# mx8m_power.net
KiCad netlist of a schematic drawn in Altium Designer
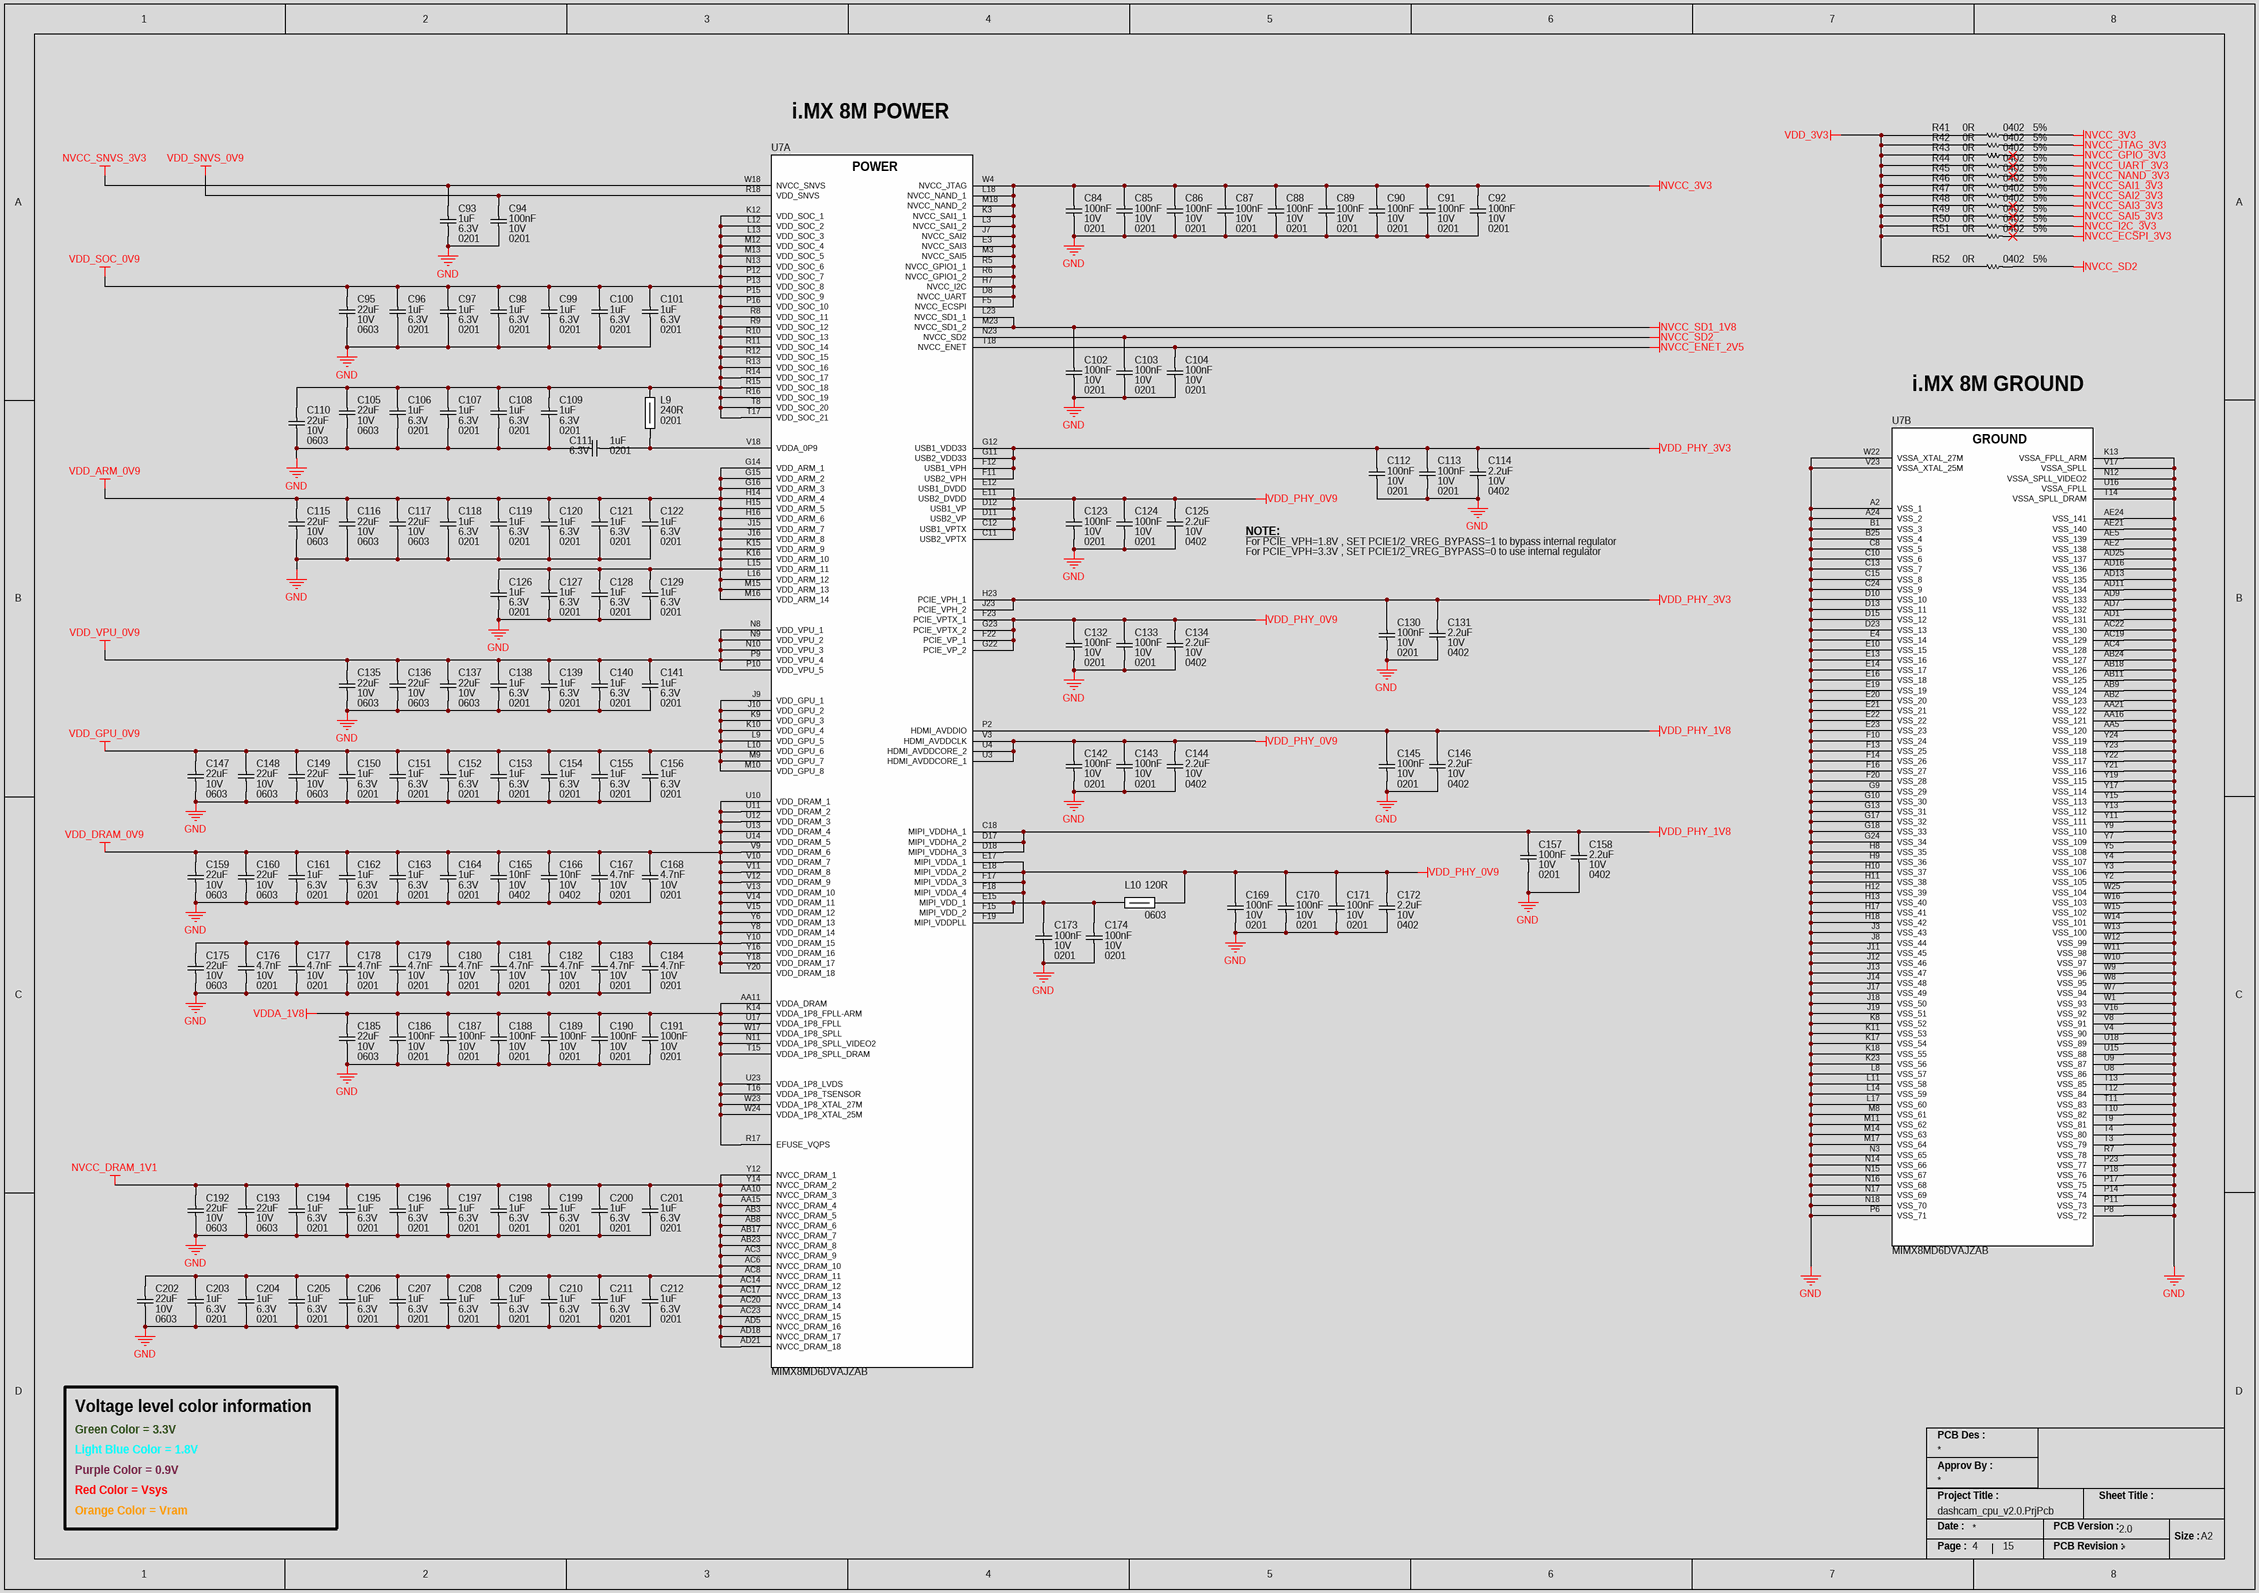
[diagram p0: mx8m_power.SchDoc]

(export (version "E")
  (design (tool "Eeschema 10.0.6"))
  (components
    (comp (ref "C84")
      (value "0201X104K100CT")
      (footprint "CAP_0201_CAPC0603X03N")
      (description "0201 0.1 uF 10 V ±10 %Tolerance X5R Surface Mount Multilayer Ceramic Capacitor")
      (fields
        (field (name "MANUFACTURER") "Walsin Technologies")
        (field (name "TOLERANCE") "10%")
        (field (name "CAPACITANCE") "100nF")
        (field (name "VOLTAGE RATING") "10V")
        (field (name "CASE/PACKAGE") "0201")
      )
      (libsource (lib "Electronic Devices_LIB") (part "CAP_0.1UF_10V_X5R_0201"))
    )
    (comp (ref "C85")
      (value "0201X104K100CT")
      (footprint "CAP_0201_CAPC0603X03N")
      (description "0201 0.1 uF 10 V ±10 %Tolerance X5R Surface Mount Multilayer Ceramic Capacitor")
      (fields
        (field (name "MANUFACTURER") "Walsin Technologies")
        (field (name "TOLERANCE") "10%")
        (field (name "CAPACITANCE") "100nF")
        (field (name "VOLTAGE RATING") "10V")
        (field (name "CASE/PACKAGE") "0201")
      )
      (libsource (lib "Electronic Devices_LIB") (part "CAP_0.1UF_10V_X5R_0201"))
    )
    (comp (ref "C86")
      (value "0201X104K100CT")
      (footprint "CAP_0201_CAPC0603X03N")
      (description "0201 0.1 uF 10 V ±10 %Tolerance X5R Surface Mount Multilayer Ceramic Capacitor")
      (fields
        (field (name "MANUFACTURER") "Walsin Technologies")
        (field (name "TOLERANCE") "10%")
        (field (name "CAPACITANCE") "100nF")
        (field (name "VOLTAGE RATING") "10V")
        (field (name "CASE/PACKAGE") "0201")
      )
      (libsource (lib "Electronic Devices_LIB") (part "CAP_0.1UF_10V_X5R_0201"))
    )
    (comp (ref "C87")
      (value "0201X104K100CT")
      (footprint "CAP_0201_CAPC0603X03N")
      (description "0201 0.1 uF 10 V ±10 %Tolerance X5R Surface Mount Multilayer Ceramic Capacitor")
      (fields
        (field (name "MANUFACTURER") "Walsin Technologies")
        (field (name "TOLERANCE") "10%")
        (field (name "CAPACITANCE") "100nF")
        (field (name "VOLTAGE RATING") "10V")
        (field (name "CASE/PACKAGE") "0201")
      )
      (libsource (lib "Electronic Devices_LIB") (part "CAP_0.1UF_10V_X5R_0201"))
    )
    (comp (ref "C88")
      (value "0201X104K100CT")
      (footprint "CAP_0201_CAPC0603X03N")
      (description "0201 0.1 uF 10 V ±10 %Tolerance X5R Surface Mount Multilayer Ceramic Capacitor")
      (fields
        (field (name "MANUFACTURER") "Walsin Technologies")
        (field (name "TOLERANCE") "10%")
        (field (name "CAPACITANCE") "100nF")
        (field (name "VOLTAGE RATING") "10V")
        (field (name "CASE/PACKAGE") "0201")
      )
      (libsource (lib "Electronic Devices_LIB") (part "CAP_0.1UF_10V_X5R_0201"))
    )
    (comp (ref "C89")
      (value "0201X104K100CT")
      (footprint "CAP_0201_CAPC0603X03N")
      (description "0201 0.1 uF 10 V ±10 %Tolerance X5R Surface Mount Multilayer Ceramic Capacitor")
      (fields
        (field (name "MANUFACTURER") "Walsin Technologies")
        (field (name "TOLERANCE") "10%")
        (field (name "CAPACITANCE") "100nF")
        (field (name "VOLTAGE RATING") "10V")
        (field (name "CASE/PACKAGE") "0201")
      )
      (libsource (lib "Electronic Devices_LIB") (part "CAP_0.1UF_10V_X5R_0201"))
    )
    (comp (ref "C90")
      (value "0201X104K100CT")
      (footprint "CAP_0201_CAPC0603X03N")
      (description "0201 0.1 uF 10 V ±10 %Tolerance X5R Surface Mount Multilayer Ceramic Capacitor")
      (fields
        (field (name "MANUFACTURER") "Walsin Technologies")
        (field (name "TOLERANCE") "10%")
        (field (name "CAPACITANCE") "100nF")
        (field (name "VOLTAGE RATING") "10V")
        (field (name "CASE/PACKAGE") "0201")
      )
      (libsource (lib "Electronic Devices_LIB") (part "CAP_0.1UF_10V_X5R_0201"))
    )
    (comp (ref "C91")
      (value "0201X104K100CT")
      (footprint "CAP_0201_CAPC0603X03N")
      (description "0201 0.1 uF 10 V ±10 %Tolerance X5R Surface Mount Multilayer Ceramic Capacitor")
      (fields
        (field (name "MANUFACTURER") "Walsin Technologies")
        (field (name "TOLERANCE") "10%")
        (field (name "CAPACITANCE") "100nF")
        (field (name "VOLTAGE RATING") "10V")
        (field (name "CASE/PACKAGE") "0201")
      )
      (libsource (lib "Electronic Devices_LIB") (part "CAP_0.1UF_10V_X5R_0201"))
    )
    (comp (ref "C92")
      (value "0201X104K100CT")
      (footprint "CAP_0201_CAPC0603X03N")
      (description "0201 0.1 uF 10 V ±10 %Tolerance X5R Surface Mount Multilayer Ceramic Capacitor")
      (fields
        (field (name "MANUFACTURER") "Walsin Technologies")
        (field (name "TOLERANCE") "10%")
        (field (name "CAPACITANCE") "100nF")
        (field (name "VOLTAGE RATING") "10V")
        (field (name "CASE/PACKAGE") "0201")
      )
      (libsource (lib "Electronic Devices_LIB") (part "CAP_0.1UF_10V_X5R_0201"))
    )
    (comp (ref "C93")
      (value "02016D105MAT2A")
      (footprint "CAP_0201_CAPC0603X03N")
      (description "0201 1 uF 6.3 V ±20 % Tolerance X5R Surface Mount Multilayer Ceramic Capacitor")
      (fields
        (field (name "MANUFACTURER") "Kyocera AVX")
        (field (name "TOLERANCE") "20%")
        (field (name "VOLTAGE RATING (DC)") "6.3V")
        (field (name "CAPACITANCE") "1uF")
        (field (name "CASE/PACKAGE") "0201")
      )
      (libsource (lib "Electronic Devices_LIB") (part "CAP_1UF_6.3V_X5R_0201"))
    )
    (comp (ref "C94")
      (value "0201X104K100CT")
      (footprint "CAP_0201_CAPC0603X03N")
      (description "0201 0.1 uF 10 V ±10 %Tolerance X5R Surface Mount Multilayer Ceramic Capacitor")
      (fields
        (field (name "MANUFACTURER") "Walsin Technologies")
        (field (name "TOLERANCE") "10%")
        (field (name "CAPACITANCE") "100nF")
        (field (name "VOLTAGE RATING") "10V")
        (field (name "CASE/PACKAGE") "0201")
      )
      (libsource (lib "Electronic Devices_LIB") (part "CAP_0.1UF_10V_X5R_0201"))
    )
    (comp (ref "C95")
      (value "C1608X5R1A226M080AC")
      (footprint "CAP_0603_CAPC1608X08N")
      (description "Multilayer Ceramic Capacitor, 22 uF, 10 V, ± 20%, X5R, 0603 [1608 Metric]")
      (fields
        (field (name "MANUFACTURER") "TDK")
        (field (name "TOLERANCE") "20%")
        (field (name "CAPACITANCE") "22uF")
        (field (name "VOLTAGE RATING") "10V")
        (field (name "CASE CODE (IMPERIAL)") "0603")
      )
      (libsource (lib "Electronic Devices_LIB") (part "CAP_22UF_10V_X5R_0603"))
    )
    (comp (ref "C96")
      (value "02016D105MAT2A")
      (footprint "CAP_0201_CAPC0603X03N")
      (description "0201 1 uF 6.3 V ±20 % Tolerance X5R Surface Mount Multilayer Ceramic Capacitor")
      (fields
        (field (name "MANUFACTURER") "Kyocera AVX")
        (field (name "TOLERANCE") "20%")
        (field (name "VOLTAGE RATING (DC)") "6.3V")
        (field (name "CAPACITANCE") "1uF")
        (field (name "CASE/PACKAGE") "0201")
      )
      (libsource (lib "Electronic Devices_LIB") (part "CAP_1UF_6.3V_X5R_0201"))
    )
    (comp (ref "C97")
      (value "02016D105MAT2A")
      (footprint "CAP_0201_CAPC0603X03N")
      (description "0201 1 uF 6.3 V ±20 % Tolerance X5R Surface Mount Multilayer Ceramic Capacitor")
      (fields
        (field (name "MANUFACTURER") "Kyocera AVX")
        (field (name "TOLERANCE") "20%")
        (field (name "VOLTAGE RATING (DC)") "6.3V")
        (field (name "CAPACITANCE") "1uF")
        (field (name "CASE/PACKAGE") "0201")
      )
      (libsource (lib "Electronic Devices_LIB") (part "CAP_1UF_6.3V_X5R_0201"))
    )
    (comp (ref "C98")
      (value "02016D105MAT2A")
      (footprint "CAP_0201_CAPC0603X03N")
      (description "0201 1 uF 6.3 V ±20 % Tolerance X5R Surface Mount Multilayer Ceramic Capacitor")
      (fields
        (field (name "MANUFACTURER") "Kyocera AVX")
        (field (name "TOLERANCE") "20%")
        (field (name "VOLTAGE RATING (DC)") "6.3V")
        (field (name "CAPACITANCE") "1uF")
        (field (name "CASE/PACKAGE") "0201")
      )
      (libsource (lib "Electronic Devices_LIB") (part "CAP_1UF_6.3V_X5R_0201"))
    )
    (comp (ref "C99")
      (value "02016D105MAT2A")
      (footprint "CAP_0201_CAPC0603X03N")
      (description "0201 1 uF 6.3 V ±20 % Tolerance X5R Surface Mount Multilayer Ceramic Capacitor")
      (fields
        (field (name "MANUFACTURER") "Kyocera AVX")
        (field (name "TOLERANCE") "20%")
        (field (name "VOLTAGE RATING (DC)") "6.3V")
        (field (name "CAPACITANCE") "1uF")
        (field (name "CASE/PACKAGE") "0201")
      )
      (libsource (lib "Electronic Devices_LIB") (part "CAP_1UF_6.3V_X5R_0201"))
    )
    (comp (ref "C100")
      (value "02016D105MAT2A")
      (footprint "CAP_0201_CAPC0603X03N")
      (description "0201 1 uF 6.3 V ±20 % Tolerance X5R Surface Mount Multilayer Ceramic Capacitor")
      (fields
        (field (name "MANUFACTURER") "Kyocera AVX")
        (field (name "TOLERANCE") "20%")
        (field (name "VOLTAGE RATING (DC)") "6.3V")
        (field (name "CAPACITANCE") "1uF")
        (field (name "CASE/PACKAGE") "0201")
      )
      (libsource (lib "Electronic Devices_LIB") (part "CAP_1UF_6.3V_X5R_0201"))
    )
    (comp (ref "C101")
      (value "02016D105MAT2A")
      (footprint "CAP_0201_CAPC0603X03N")
      (description "0201 1 uF 6.3 V ±20 % Tolerance X5R Surface Mount Multilayer Ceramic Capacitor")
      (fields
        (field (name "MANUFACTURER") "Kyocera AVX")
        (field (name "TOLERANCE") "20%")
        (field (name "VOLTAGE RATING (DC)") "6.3V")
        (field (name "CAPACITANCE") "1uF")
        (field (name "CASE/PACKAGE") "0201")
      )
      (libsource (lib "Electronic Devices_LIB") (part "CAP_1UF_6.3V_X5R_0201"))
    )
    (comp (ref "C102")
      (value "0201X104K100CT")
      (footprint "CAP_0201_CAPC0603X03N")
      (description "0201 0.1 uF 10 V ±10 %Tolerance X5R Surface Mount Multilayer Ceramic Capacitor")
      (fields
        (field (name "MANUFACTURER") "Walsin Technologies")
        (field (name "TOLERANCE") "10%")
        (field (name "CAPACITANCE") "100nF")
        (field (name "VOLTAGE RATING") "10V")
        (field (name "CASE/PACKAGE") "0201")
      )
      (libsource (lib "Electronic Devices_LIB") (part "CAP_0.1UF_10V_X5R_0201"))
    )
    (comp (ref "C103")
      (value "0201X104K100CT")
      (footprint "CAP_0201_CAPC0603X03N")
      (description "0201 0.1 uF 10 V ±10 %Tolerance X5R Surface Mount Multilayer Ceramic Capacitor")
      (fields
        (field (name "MANUFACTURER") "Walsin Technologies")
        (field (name "TOLERANCE") "10%")
        (field (name "CAPACITANCE") "100nF")
        (field (name "VOLTAGE RATING") "10V")
        (field (name "CASE/PACKAGE") "0201")
      )
      (libsource (lib "Electronic Devices_LIB") (part "CAP_0.1UF_10V_X5R_0201"))
    )
    (comp (ref "C104")
      (value "0201X104K100CT")
      (footprint "CAP_0201_CAPC0603X03N")
      (description "0201 0.1 uF 10 V ±10 %Tolerance X5R Surface Mount Multilayer Ceramic Capacitor")
      (fields
        (field (name "MANUFACTURER") "Walsin Technologies")
        (field (name "TOLERANCE") "10%")
        (field (name "CAPACITANCE") "100nF")
        (field (name "VOLTAGE RATING") "10V")
        (field (name "CASE/PACKAGE") "0201")
      )
      (libsource (lib "Electronic Devices_LIB") (part "CAP_0.1UF_10V_X5R_0201"))
    )
    (comp (ref "C105")
      (value "C1608X5R1A226M080AC")
      (footprint "CAP_0603_CAPC1608X08N")
      (description "Multilayer Ceramic Capacitor, 22 uF, 10 V, ± 20%, X5R, 0603 [1608 Metric]")
      (fields
        (field (name "MANUFACTURER") "TDK")
        (field (name "TOLERANCE") "20%")
        (field (name "CAPACITANCE") "22uF")
        (field (name "VOLTAGE RATING") "10V")
        (field (name "CASE CODE (IMPERIAL)") "0603")
      )
      (libsource (lib "Electronic Devices_LIB") (part "CAP_22UF_10V_X5R_0603"))
    )
    (comp (ref "C106")
      (value "02016D105MAT2A")
      (footprint "CAP_0201_CAPC0603X03N")
      (description "0201 1 uF 6.3 V ±20 % Tolerance X5R Surface Mount Multilayer Ceramic Capacitor")
      (fields
        (field (name "MANUFACTURER") "Kyocera AVX")
        (field (name "TOLERANCE") "20%")
        (field (name "VOLTAGE RATING (DC)") "6.3V")
        (field (name "CAPACITANCE") "1uF")
        (field (name "CASE/PACKAGE") "0201")
      )
      (libsource (lib "Electronic Devices_LIB") (part "CAP_1UF_6.3V_X5R_0201"))
    )
    (comp (ref "C107")
      (value "02016D105MAT2A")
      (footprint "CAP_0201_CAPC0603X03N")
      (description "0201 1 uF 6.3 V ±20 % Tolerance X5R Surface Mount Multilayer Ceramic Capacitor")
      (fields
        (field (name "MANUFACTURER") "Kyocera AVX")
        (field (name "TOLERANCE") "20%")
        (field (name "VOLTAGE RATING (DC)") "6.3V")
        (field (name "CAPACITANCE") "1uF")
        (field (name "CASE/PACKAGE") "0201")
      )
      (libsource (lib "Electronic Devices_LIB") (part "CAP_1UF_6.3V_X5R_0201"))
    )
    (comp (ref "C108")
      (value "02016D105MAT2A")
      (footprint "CAP_0201_CAPC0603X03N")
      (description "0201 1 uF 6.3 V ±20 % Tolerance X5R Surface Mount Multilayer Ceramic Capacitor")
      (fields
        (field (name "MANUFACTURER") "Kyocera AVX")
        (field (name "TOLERANCE") "20%")
        (field (name "VOLTAGE RATING (DC)") "6.3V")
        (field (name "CAPACITANCE") "1uF")
        (field (name "CASE/PACKAGE") "0201")
      )
      (libsource (lib "Electronic Devices_LIB") (part "CAP_1UF_6.3V_X5R_0201"))
    )
    (comp (ref "C109")
      (value "02016D105MAT2A")
      (footprint "CAP_0201_CAPC0603X03N")
      (description "0201 1 uF 6.3 V ±20 % Tolerance X5R Surface Mount Multilayer Ceramic Capacitor")
      (fields
        (field (name "MANUFACTURER") "Kyocera AVX")
        (field (name "TOLERANCE") "20%")
        (field (name "VOLTAGE RATING (DC)") "6.3V")
        (field (name "CAPACITANCE") "1uF")
        (field (name "CASE/PACKAGE") "0201")
      )
      (libsource (lib "Electronic Devices_LIB") (part "CAP_1UF_6.3V_X5R_0201"))
    )
    (comp (ref "C110")
      (value "C1608X5R1A226M080AC")
      (footprint "CAP_0603_CAPC1608X08N")
      (description "Multilayer Ceramic Capacitor, 22 uF, 10 V, ± 20%, X5R, 0603 [1608 Metric]")
      (fields
        (field (name "MANUFACTURER") "TDK")
        (field (name "TOLERANCE") "20%")
        (field (name "CAPACITANCE") "22uF")
        (field (name "VOLTAGE RATING") "10V")
        (field (name "CASE CODE (IMPERIAL)") "0603")
      )
      (libsource (lib "Electronic Devices_LIB") (part "CAP_22UF_10V_X5R_0603"))
    )
    (comp (ref "C111")
      (value "02016D105MAT2A")
      (footprint "CAP_0201_CAPC0603X03N")
      (description "0201 1 uF 6.3 V ±20 % Tolerance X5R Surface Mount Multilayer Ceramic Capacitor")
      (fields
        (field (name "MANUFACTURER") "Kyocera AVX")
        (field (name "TOLERANCE") "20%")
        (field (name "VOLTAGE RATING (DC)") "6.3V")
        (field (name "CAPACITANCE") "1uF")
        (field (name "CASE/PACKAGE") "0201")
      )
      (libsource (lib "Electronic Devices_LIB") (part "CAP_1UF_6.3V_X5R_0201"))
    )
    (comp (ref "C112")
      (value "0201X104K100CT")
      (footprint "CAP_0201_CAPC0603X03N")
      (description "0201 0.1 uF 10 V ±10 %Tolerance X5R Surface Mount Multilayer Ceramic Capacitor")
      (fields
        (field (name "MANUFACTURER") "Walsin Technologies")
        (field (name "TOLERANCE") "10%")
        (field (name "CAPACITANCE") "100nF")
        (field (name "VOLTAGE RATING") "10V")
        (field (name "CASE/PACKAGE") "0201")
      )
      (libsource (lib "Electronic Devices_LIB") (part "CAP_0.1UF_10V_X5R_0201"))
    )
    (comp (ref "C113")
      (value "0201X104K100CT")
      (footprint "CAP_0201_CAPC0603X03N")
      (description "0201 0.1 uF 10 V ±10 %Tolerance X5R Surface Mount Multilayer Ceramic Capacitor")
      (fields
        (field (name "MANUFACTURER") "Walsin Technologies")
        (field (name "TOLERANCE") "10%")
        (field (name "CAPACITANCE") "100nF")
        (field (name "VOLTAGE RATING") "10V")
        (field (name "CASE/PACKAGE") "0201")
      )
      (libsource (lib "Electronic Devices_LIB") (part "CAP_0.1UF_10V_X5R_0201"))
    )
    (comp (ref "C114")
      (value "C1005X5R1A225K050BC")
      (footprint "CAP_0201_CAPC0603X03N")
      (description "Multilayer Ceramic Capacitor, 2.2 uF, 10 V, ± 10%, X5R, 0402 [1005 Metric]")
      (fields
        (field (name "MANUFACTURER") "TDK")
        (field (name "TOLERANCE") "10%")
        (field (name "VOLTAGE RATING (DC)") "10V")
        (field (name "CAPACITANCE") "2.2uF")
        (field (name "CASE/PACKAGE") "0402")
      )
      (libsource (lib "Electronic Devices_LIB") (part "CAP_2.2UF_10V_X5R_0402"))
    )
    (comp (ref "C115")
      (value "C1608X5R1A226M080AC")
      (footprint "CAP_0603_CAPC1608X08N")
      (description "Multilayer Ceramic Capacitor, 22 uF, 10 V, ± 20%, X5R, 0603 [1608 Metric]")
      (fields
        (field (name "MANUFACTURER") "TDK")
        (field (name "TOLERANCE") "20%")
        (field (name "CAPACITANCE") "22uF")
        (field (name "VOLTAGE RATING") "10V")
        (field (name "CASE CODE (IMPERIAL)") "0603")
      )
      (libsource (lib "Electronic Devices_LIB") (part "CAP_22UF_10V_X5R_0603"))
    )
    (comp (ref "C116")
      (value "C1608X5R1A226M080AC")
      (footprint "CAP_0603_CAPC1608X08N")
      (description "Multilayer Ceramic Capacitor, 22 uF, 10 V, ± 20%, X5R, 0603 [1608 Metric]")
      (fields
        (field (name "MANUFACTURER") "TDK")
        (field (name "TOLERANCE") "20%")
        (field (name "CAPACITANCE") "22uF")
        (field (name "VOLTAGE RATING") "10V")
        (field (name "CASE CODE (IMPERIAL)") "0603")
      )
      (libsource (lib "Electronic Devices_LIB") (part "CAP_22UF_10V_X5R_0603"))
    )
    (comp (ref "C117")
      (value "C1608X5R1A226M080AC")
      (footprint "CAP_0603_CAPC1608X08N")
      (description "Multilayer Ceramic Capacitor, 22 uF, 10 V, ± 20%, X5R, 0603 [1608 Metric]")
      (fields
        (field (name "MANUFACTURER") "TDK")
        (field (name "TOLERANCE") "20%")
        (field (name "CAPACITANCE") "22uF")
        (field (name "VOLTAGE RATING") "10V")
        (field (name "CASE CODE (IMPERIAL)") "0603")
      )
      (libsource (lib "Electronic Devices_LIB") (part "CAP_22UF_10V_X5R_0603"))
    )
    (comp (ref "C118")
      (value "02016D105MAT2A")
      (footprint "CAP_0201_CAPC0603X03N")
      (description "0201 1 uF 6.3 V ±20 % Tolerance X5R Surface Mount Multilayer Ceramic Capacitor")
      (fields
        (field (name "MANUFACTURER") "Kyocera AVX")
        (field (name "TOLERANCE") "20%")
        (field (name "VOLTAGE RATING (DC)") "6.3V")
        (field (name "CAPACITANCE") "1uF")
        (field (name "CASE/PACKAGE") "0201")
      )
      (libsource (lib "Electronic Devices_LIB") (part "CAP_1UF_6.3V_X5R_0201"))
    )
    (comp (ref "C119")
      (value "02016D105MAT2A")
      (footprint "CAP_0201_CAPC0603X03N")
      (description "0201 1 uF 6.3 V ±20 % Tolerance X5R Surface Mount Multilayer Ceramic Capacitor")
      (fields
        (field (name "MANUFACTURER") "Kyocera AVX")
        (field (name "TOLERANCE") "20%")
        (field (name "VOLTAGE RATING (DC)") "6.3V")
        (field (name "CAPACITANCE") "1uF")
        (field (name "CASE/PACKAGE") "0201")
      )
      (libsource (lib "Electronic Devices_LIB") (part "CAP_1UF_6.3V_X5R_0201"))
    )
    (comp (ref "C120")
      (value "02016D105MAT2A")
      (footprint "CAP_0201_CAPC0603X03N")
      (description "0201 1 uF 6.3 V ±20 % Tolerance X5R Surface Mount Multilayer Ceramic Capacitor")
      (fields
        (field (name "MANUFACTURER") "Kyocera AVX")
        (field (name "TOLERANCE") "20%")
        (field (name "VOLTAGE RATING (DC)") "6.3V")
        (field (name "CAPACITANCE") "1uF")
        (field (name "CASE/PACKAGE") "0201")
      )
      (libsource (lib "Electronic Devices_LIB") (part "CAP_1UF_6.3V_X5R_0201"))
    )
    (comp (ref "C121")
      (value "02016D105MAT2A")
      (footprint "CAP_0201_CAPC0603X03N")
      (description "0201 1 uF 6.3 V ±20 % Tolerance X5R Surface Mount Multilayer Ceramic Capacitor")
      (fields
        (field (name "MANUFACTURER") "Kyocera AVX")
        (field (name "TOLERANCE") "20%")
        (field (name "VOLTAGE RATING (DC)") "6.3V")
        (field (name "CAPACITANCE") "1uF")
        (field (name "CASE/PACKAGE") "0201")
      )
      (libsource (lib "Electronic Devices_LIB") (part "CAP_1UF_6.3V_X5R_0201"))
    )
    (comp (ref "C122")
      (value "02016D105MAT2A")
      (footprint "CAP_0201_CAPC0603X03N")
      (description "0201 1 uF 6.3 V ±20 % Tolerance X5R Surface Mount Multilayer Ceramic Capacitor")
      (fields
        (field (name "MANUFACTURER") "Kyocera AVX")
        (field (name "TOLERANCE") "20%")
        (field (name "VOLTAGE RATING (DC)") "6.3V")
        (field (name "CAPACITANCE") "1uF")
        (field (name "CASE/PACKAGE") "0201")
      )
      (libsource (lib "Electronic Devices_LIB") (part "CAP_1UF_6.3V_X5R_0201"))
    )
    (comp (ref "C123")
      (value "0201X104K100CT")
      (footprint "CAP_0201_CAPC0603X03N")
      (description "0201 0.1 uF 10 V ±10 %Tolerance X5R Surface Mount Multilayer Ceramic Capacitor")
      (fields
        (field (name "MANUFACTURER") "Walsin Technologies")
        (field (name "TOLERANCE") "10%")
        (field (name "CAPACITANCE") "100nF")
        (field (name "VOLTAGE RATING") "10V")
        (field (name "CASE/PACKAGE") "0201")
      )
      (libsource (lib "Electronic Devices_LIB") (part "CAP_0.1UF_10V_X5R_0201"))
    )
    (comp (ref "C124")
      (value "0201X104K100CT")
      (footprint "CAP_0201_CAPC0603X03N")
      (description "0201 0.1 uF 10 V ±10 %Tolerance X5R Surface Mount Multilayer Ceramic Capacitor")
      (fields
        (field (name "MANUFACTURER") "Walsin Technologies")
        (field (name "TOLERANCE") "10%")
        (field (name "CAPACITANCE") "100nF")
        (field (name "VOLTAGE RATING") "10V")
        (field (name "CASE/PACKAGE") "0201")
      )
      (libsource (lib "Electronic Devices_LIB") (part "CAP_0.1UF_10V_X5R_0201"))
    )
    (comp (ref "C125")
      (value "C1005X5R1A225K050BC")
      (footprint "CAP_0201_CAPC0603X03N")
      (description "Multilayer Ceramic Capacitor, 2.2 uF, 10 V, ± 10%, X5R, 0402 [1005 Metric]")
      (fields
        (field (name "MANUFACTURER") "TDK")
        (field (name "TOLERANCE") "10%")
        (field (name "VOLTAGE RATING (DC)") "10V")
        (field (name "CAPACITANCE") "2.2uF")
        (field (name "CASE/PACKAGE") "0402")
      )
      (libsource (lib "Electronic Devices_LIB") (part "CAP_2.2UF_10V_X5R_0402"))
    )
    (comp (ref "C126")
      (value "02016D105MAT2A")
      (footprint "CAP_0201_CAPC0603X03N")
      (description "0201 1 uF 6.3 V ±20 % Tolerance X5R Surface Mount Multilayer Ceramic Capacitor")
      (fields
        (field (name "MANUFACTURER") "Kyocera AVX")
        (field (name "TOLERANCE") "20%")
        (field (name "VOLTAGE RATING (DC)") "6.3V")
        (field (name "CAPACITANCE") "1uF")
        (field (name "CASE/PACKAGE") "0201")
      )
      (libsource (lib "Electronic Devices_LIB") (part "CAP_1UF_6.3V_X5R_0201"))
    )
    (comp (ref "C127")
      (value "02016D105MAT2A")
      (footprint "CAP_0201_CAPC0603X03N")
      (description "0201 1 uF 6.3 V ±20 % Tolerance X5R Surface Mount Multilayer Ceramic Capacitor")
      (fields
        (field (name "MANUFACTURER") "Kyocera AVX")
        (field (name "TOLERANCE") "20%")
        (field (name "VOLTAGE RATING (DC)") "6.3V")
        (field (name "CAPACITANCE") "1uF")
        (field (name "CASE/PACKAGE") "0201")
      )
      (libsource (lib "Electronic Devices_LIB") (part "CAP_1UF_6.3V_X5R_0201"))
    )
    (comp (ref "C128")
      (value "02016D105MAT2A")
      (footprint "CAP_0201_CAPC0603X03N")
      (description "0201 1 uF 6.3 V ±20 % Tolerance X5R Surface Mount Multilayer Ceramic Capacitor")
      (fields
        (field (name "MANUFACTURER") "Kyocera AVX")
        (field (name "TOLERANCE") "20%")
        (field (name "VOLTAGE RATING (DC)") "6.3V")
        (field (name "CAPACITANCE") "1uF")
        (field (name "CASE/PACKAGE") "0201")
      )
      (libsource (lib "Electronic Devices_LIB") (part "CAP_1UF_6.3V_X5R_0201"))
    )
    (comp (ref "C129")
      (value "02016D105MAT2A")
      (footprint "CAP_0201_CAPC0603X03N")
      (description "0201 1 uF 6.3 V ±20 % Tolerance X5R Surface Mount Multilayer Ceramic Capacitor")
      (fields
        (field (name "MANUFACTURER") "Kyocera AVX")
        (field (name "TOLERANCE") "20%")
        (field (name "VOLTAGE RATING (DC)") "6.3V")
        (field (name "CAPACITANCE") "1uF")
        (field (name "CASE/PACKAGE") "0201")
      )
      (libsource (lib "Electronic Devices_LIB") (part "CAP_1UF_6.3V_X5R_0201"))
    )
    (comp (ref "C130")
      (value "0201X104K100CT")
      (footprint "CAP_0201_CAPC0603X03N")
      (description "0201 0.1 uF 10 V ±10 %Tolerance X5R Surface Mount Multilayer Ceramic Capacitor")
      (fields
        (field (name "MANUFACTURER") "Walsin Technologies")
        (field (name "TOLERANCE") "10%")
        (field (name "CAPACITANCE") "100nF")
        (field (name "VOLTAGE RATING") "10V")
        (field (name "CASE/PACKAGE") "0201")
      )
      (libsource (lib "Electronic Devices_LIB") (part "CAP_0.1UF_10V_X5R_0201"))
    )
    (comp (ref "C131")
      (value "C1005X5R1A225K050BC")
      (footprint "CAP_0201_CAPC0603X03N")
      (description "Multilayer Ceramic Capacitor, 2.2 uF, 10 V, ± 10%, X5R, 0402 [1005 Metric]")
      (fields
        (field (name "MANUFACTURER") "TDK")
        (field (name "TOLERANCE") "10%")
        (field (name "VOLTAGE RATING (DC)") "10V")
        (field (name "CAPACITANCE") "2.2uF")
        (field (name "CASE/PACKAGE") "0402")
      )
      (libsource (lib "Electronic Devices_LIB") (part "CAP_2.2UF_10V_X5R_0402"))
    )
    (comp (ref "C132")
      (value "0201X104K100CT")
      (footprint "CAP_0201_CAPC0603X03N")
      (description "0201 0.1 uF 10 V ±10 %Tolerance X5R Surface Mount Multilayer Ceramic Capacitor")
      (fields
        (field (name "MANUFACTURER") "Walsin Technologies")
        (field (name "TOLERANCE") "10%")
        (field (name "CAPACITANCE") "100nF")
        (field (name "VOLTAGE RATING") "10V")
        (field (name "CASE/PACKAGE") "0201")
      )
      (libsource (lib "Electronic Devices_LIB") (part "CAP_0.1UF_10V_X5R_0201"))
    )
    (comp (ref "C133")
      (value "0201X104K100CT")
      (footprint "CAP_0201_CAPC0603X03N")
      (description "0201 0.1 uF 10 V ±10 %Tolerance X5R Surface Mount Multilayer Ceramic Capacitor")
      (fields
        (field (name "MANUFACTURER") "Walsin Technologies")
        (field (name "TOLERANCE") "10%")
        (field (name "CAPACITANCE") "100nF")
        (field (name "VOLTAGE RATING") "10V")
        (field (name "CASE/PACKAGE") "0201")
      )
      (libsource (lib "Electronic Devices_LIB") (part "CAP_0.1UF_10V_X5R_0201"))
    )
    (comp (ref "C134")
      (value "C1005X5R1A225K050BC")
      (footprint "CAP_0201_CAPC0603X03N")
      (description "Multilayer Ceramic Capacitor, 2.2 uF, 10 V, ± 10%, X5R, 0402 [1005 Metric]")
      (fields
        (field (name "MANUFACTURER") "TDK")
        (field (name "TOLERANCE") "10%")
        (field (name "VOLTAGE RATING (DC)") "10V")
        (field (name "CAPACITANCE") "2.2uF")
        (field (name "CASE/PACKAGE") "0402")
      )
      (libsource (lib "Electronic Devices_LIB") (part "CAP_2.2UF_10V_X5R_0402"))
    )
    (comp (ref "C135")
      (value "C1608X5R1A226M080AC")
      (footprint "CAP_0603_CAPC1608X08N")
      (description "Multilayer Ceramic Capacitor, 22 uF, 10 V, ± 20%, X5R, 0603 [1608 Metric]")
      (fields
        (field (name "MANUFACTURER") "TDK")
        (field (name "TOLERANCE") "20%")
        (field (name "CAPACITANCE") "22uF")
        (field (name "VOLTAGE RATING") "10V")
        (field (name "CASE CODE (IMPERIAL)") "0603")
      )
      (libsource (lib "Electronic Devices_LIB") (part "CAP_22UF_10V_X5R_0603"))
    )
    (comp (ref "C136")
      (value "C1608X5R1A226M080AC")
      (footprint "CAP_0603_CAPC1608X08N")
      (description "Multilayer Ceramic Capacitor, 22 uF, 10 V, ± 20%, X5R, 0603 [1608 Metric]")
      (fields
        (field (name "MANUFACTURER") "TDK")
        (field (name "TOLERANCE") "20%")
        (field (name "CAPACITANCE") "22uF")
        (field (name "VOLTAGE RATING") "10V")
        (field (name "CASE CODE (IMPERIAL)") "0603")
      )
      (libsource (lib "Electronic Devices_LIB") (part "CAP_22UF_10V_X5R_0603"))
    )
    (comp (ref "C137")
      (value "C1608X5R1A226M080AC")
      (footprint "CAP_0603_CAPC1608X08N")
      (description "Multilayer Ceramic Capacitor, 22 uF, 10 V, ± 20%, X5R, 0603 [1608 Metric]")
      (fields
        (field (name "MANUFACTURER") "TDK")
        (field (name "TOLERANCE") "20%")
        (field (name "CAPACITANCE") "22uF")
        (field (name "VOLTAGE RATING") "10V")
        (field (name "CASE CODE (IMPERIAL)") "0603")
      )
      (libsource (lib "Electronic Devices_LIB") (part "CAP_22UF_10V_X5R_0603"))
    )
    (comp (ref "C138")
      (value "02016D105MAT2A")
      (footprint "CAP_0201_CAPC0603X03N")
      (description "0201 1 uF 6.3 V ±20 % Tolerance X5R Surface Mount Multilayer Ceramic Capacitor")
      (fields
        (field (name "MANUFACTURER") "Kyocera AVX")
        (field (name "TOLERANCE") "20%")
        (field (name "VOLTAGE RATING (DC)") "6.3V")
        (field (name "CAPACITANCE") "1uF")
        (field (name "CASE/PACKAGE") "0201")
      )
      (libsource (lib "Electronic Devices_LIB") (part "CAP_1UF_6.3V_X5R_0201"))
    )
    (comp (ref "C139")
      (value "02016D105MAT2A")
      (footprint "CAP_0201_CAPC0603X03N")
      (description "0201 1 uF 6.3 V ±20 % Tolerance X5R Surface Mount Multilayer Ceramic Capacitor")
      (fields
        (field (name "MANUFACTURER") "Kyocera AVX")
        (field (name "TOLERANCE") "20%")
        (field (name "VOLTAGE RATING (DC)") "6.3V")
        (field (name "CAPACITANCE") "1uF")
        (field (name "CASE/PACKAGE") "0201")
      )
      (libsource (lib "Electronic Devices_LIB") (part "CAP_1UF_6.3V_X5R_0201"))
    )
    (comp (ref "C140")
      (value "02016D105MAT2A")
      (footprint "CAP_0201_CAPC0603X03N")
      (description "0201 1 uF 6.3 V ±20 % Tolerance X5R Surface Mount Multilayer Ceramic Capacitor")
      (fields
        (field (name "MANUFACTURER") "Kyocera AVX")
        (field (name "TOLERANCE") "20%")
        (field (name "VOLTAGE RATING (DC)") "6.3V")
        (field (name "CAPACITANCE") "1uF")
        (field (name "CASE/PACKAGE") "0201")
      )
      (libsource (lib "Electronic Devices_LIB") (part "CAP_1UF_6.3V_X5R_0201"))
    )
    (comp (ref "C141")
      (value "02016D105MAT2A")
      (footprint "CAP_0201_CAPC0603X03N")
      (description "0201 1 uF 6.3 V ±20 % Tolerance X5R Surface Mount Multilayer Ceramic Capacitor")
      (fields
        (field (name "MANUFACTURER") "Kyocera AVX")
        (field (name "TOLERANCE") "20%")
        (field (name "VOLTAGE RATING (DC)") "6.3V")
        (field (name "CAPACITANCE") "1uF")
        (field (name "CASE/PACKAGE") "0201")
      )
      (libsource (lib "Electronic Devices_LIB") (part "CAP_1UF_6.3V_X5R_0201"))
    )
    (comp (ref "C142")
      (value "0201X104K100CT")
      (footprint "CAP_0201_CAPC0603X03N")
      (description "0201 0.1 uF 10 V ±10 %Tolerance X5R Surface Mount Multilayer Ceramic Capacitor")
      (fields
        (field (name "MANUFACTURER") "Walsin Technologies")
        (field (name "TOLERANCE") "10%")
        (field (name "CAPACITANCE") "100nF")
        (field (name "VOLTAGE RATING") "10V")
        (field (name "CASE/PACKAGE") "0201")
      )
      (libsource (lib "Electronic Devices_LIB") (part "CAP_0.1UF_10V_X5R_0201"))
    )
    (comp (ref "C143")
      (value "0201X104K100CT")
      (footprint "CAP_0201_CAPC0603X03N")
      (description "0201 0.1 uF 10 V ±10 %Tolerance X5R Surface Mount Multilayer Ceramic Capacitor")
      (fields
        (field (name "MANUFACTURER") "Walsin Technologies")
        (field (name "TOLERANCE") "10%")
        (field (name "CAPACITANCE") "100nF")
        (field (name "VOLTAGE RATING") "10V")
        (field (name "CASE/PACKAGE") "0201")
      )
      (libsource (lib "Electronic Devices_LIB") (part "CAP_0.1UF_10V_X5R_0201"))
    )
    (comp (ref "C144")
      (value "C1005X5R1A225K050BC")
      (footprint "CAP_0201_CAPC0603X03N")
      (description "Multilayer Ceramic Capacitor, 2.2 uF, 10 V, ± 10%, X5R, 0402 [1005 Metric]")
      (fields
        (field (name "MANUFACTURER") "TDK")
        (field (name "TOLERANCE") "10%")
        (field (name "VOLTAGE RATING (DC)") "10V")
        (field (name "CAPACITANCE") "2.2uF")
        (field (name "CASE/PACKAGE") "0402")
      )
      (libsource (lib "Electronic Devices_LIB") (part "CAP_2.2UF_10V_X5R_0402"))
    )
    (comp (ref "C145")
      (value "0201X104K100CT")
      (footprint "CAP_0201_CAPC0603X03N")
      (description "0201 0.1 uF 10 V ±10 %Tolerance X5R Surface Mount Multilayer Ceramic Capacitor")
      (fields
        (field (name "MANUFACTURER") "Walsin Technologies")
        (field (name "TOLERANCE") "10%")
        (field (name "CAPACITANCE") "100nF")
        (field (name "VOLTAGE RATING") "10V")
        (field (name "CASE/PACKAGE") "0201")
      )
      (libsource (lib "Electronic Devices_LIB") (part "CAP_0.1UF_10V_X5R_0201"))
    )
    (comp (ref "C146")
      (value "C1005X5R1A225K050BC")
      (footprint "CAP_0201_CAPC0603X03N")
      (description "Multilayer Ceramic Capacitor, 2.2 uF, 10 V, ± 10%, X5R, 0402 [1005 Metric]")
      (fields
        (field (name "MANUFACTURER") "TDK")
        (field (name "TOLERANCE") "10%")
        (field (name "VOLTAGE RATING (DC)") "10V")
        (field (name "CAPACITANCE") "2.2uF")
        (field (name "CASE/PACKAGE") "0402")
      )
      (libsource (lib "Electronic Devices_LIB") (part "CAP_2.2UF_10V_X5R_0402"))
    )
    (comp (ref "C147")
      (value "C1608X5R1A226M080AC")
      (footprint "CAP_0603_CAPC1608X08N")
      (description "Multilayer Ceramic Capacitor, 22 uF, 10 V, ± 20%, X5R, 0603 [1608 Metric]")
      (fields
        (field (name "MANUFACTURER") "TDK")
        (field (name "TOLERANCE") "20%")
        (field (name "CAPACITANCE") "22uF")
        (field (name "VOLTAGE RATING") "10V")
        (field (name "CASE CODE (IMPERIAL)") "0603")
      )
      (libsource (lib "Electronic Devices_LIB") (part "CAP_22UF_10V_X5R_0603"))
    )
    (comp (ref "C148")
      (value "C1608X5R1A226M080AC")
      (footprint "CAP_0603_CAPC1608X08N")
      (description "Multilayer Ceramic Capacitor, 22 uF, 10 V, ± 20%, X5R, 0603 [1608 Metric]")
      (fields
        (field (name "MANUFACTURER") "TDK")
        (field (name "TOLERANCE") "20%")
        (field (name "CAPACITANCE") "22uF")
        (field (name "VOLTAGE RATING") "10V")
        (field (name "CASE CODE (IMPERIAL)") "0603")
      )
      (libsource (lib "Electronic Devices_LIB") (part "CAP_22UF_10V_X5R_0603"))
    )
    (comp (ref "C149")
      (value "C1608X5R1A226M080AC")
      (footprint "CAP_0603_CAPC1608X08N")
      (description "Multilayer Ceramic Capacitor, 22 uF, 10 V, ± 20%, X5R, 0603 [1608 Metric]")
      (fields
        (field (name "MANUFACTURER") "TDK")
        (field (name "TOLERANCE") "20%")
        (field (name "CAPACITANCE") "22uF")
        (field (name "VOLTAGE RATING") "10V")
        (field (name "CASE CODE (IMPERIAL)") "0603")
      )
      (libsource (lib "Electronic Devices_LIB") (part "CAP_22UF_10V_X5R_0603"))
    )
    (comp (ref "C150")
      (value "02016D105MAT2A")
      (footprint "CAP_0201_CAPC0603X03N")
      (description "0201 1 uF 6.3 V ±20 % Tolerance X5R Surface Mount Multilayer Ceramic Capacitor")
      (fields
        (field (name "MANUFACTURER") "Kyocera AVX")
        (field (name "TOLERANCE") "20%")
        (field (name "VOLTAGE RATING (DC)") "6.3V")
        (field (name "CAPACITANCE") "1uF")
        (field (name "CASE/PACKAGE") "0201")
      )
      (libsource (lib "Electronic Devices_LIB") (part "CAP_1UF_6.3V_X5R_0201"))
    )
    (comp (ref "C151")
      (value "02016D105MAT2A")
      (footprint "CAP_0201_CAPC0603X03N")
      (description "0201 1 uF 6.3 V ±20 % Tolerance X5R Surface Mount Multilayer Ceramic Capacitor")
      (fields
        (field (name "MANUFACTURER") "Kyocera AVX")
        (field (name "TOLERANCE") "20%")
        (field (name "VOLTAGE RATING (DC)") "6.3V")
        (field (name "CAPACITANCE") "1uF")
        (field (name "CASE/PACKAGE") "0201")
      )
      (libsource (lib "Electronic Devices_LIB") (part "CAP_1UF_6.3V_X5R_0201"))
    )
    (comp (ref "C152")
      (value "02016D105MAT2A")
      (footprint "CAP_0201_CAPC0603X03N")
      (description "0201 1 uF 6.3 V ±20 % Tolerance X5R Surface Mount Multilayer Ceramic Capacitor")
      (fields
        (field (name "MANUFACTURER") "Kyocera AVX")
        (field (name "TOLERANCE") "20%")
        (field (name "VOLTAGE RATING (DC)") "6.3V")
        (field (name "CAPACITANCE") "1uF")
        (field (name "CASE/PACKAGE") "0201")
      )
      (libsource (lib "Electronic Devices_LIB") (part "CAP_1UF_6.3V_X5R_0201"))
    )
    (comp (ref "C153")
      (value "02016D105MAT2A")
      (footprint "CAP_0201_CAPC0603X03N")
      (description "0201 1 uF 6.3 V ±20 % Tolerance X5R Surface Mount Multilayer Ceramic Capacitor")
      (fields
        (field (name "MANUFACTURER") "Kyocera AVX")
        (field (name "TOLERANCE") "20%")
        (field (name "VOLTAGE RATING (DC)") "6.3V")
        (field (name "CAPACITANCE") "1uF")
        (field (name "CASE/PACKAGE") "0201")
      )
      (libsource (lib "Electronic Devices_LIB") (part "CAP_1UF_6.3V_X5R_0201"))
    )
    (comp (ref "C154")
      (value "02016D105MAT2A")
      (footprint "CAP_0201_CAPC0603X03N")
      (description "0201 1 uF 6.3 V ±20 % Tolerance X5R Surface Mount Multilayer Ceramic Capacitor")
      (fields
        (field (name "MANUFACTURER") "Kyocera AVX")
        (field (name "TOLERANCE") "20%")
        (field (name "VOLTAGE RATING (DC)") "6.3V")
        (field (name "CAPACITANCE") "1uF")
        (field (name "CASE/PACKAGE") "0201")
      )
      (libsource (lib "Electronic Devices_LIB") (part "CAP_1UF_6.3V_X5R_0201"))
    )
    (comp (ref "C155")
      (value "02016D105MAT2A")
      (footprint "CAP_0201_CAPC0603X03N")
      (description "0201 1 uF 6.3 V ±20 % Tolerance X5R Surface Mount Multilayer Ceramic Capacitor")
      (fields
        (field (name "MANUFACTURER") "Kyocera AVX")
        (field (name "TOLERANCE") "20%")
        (field (name "VOLTAGE RATING (DC)") "6.3V")
        (field (name "CAPACITANCE") "1uF")
        (field (name "CASE/PACKAGE") "0201")
      )
      (libsource (lib "Electronic Devices_LIB") (part "CAP_1UF_6.3V_X5R_0201"))
    )
    (comp (ref "C156")
      (value "02016D105MAT2A")
      (footprint "CAP_0201_CAPC0603X03N")
      (description "0201 1 uF 6.3 V ±20 % Tolerance X5R Surface Mount Multilayer Ceramic Capacitor")
      (fields
        (field (name "MANUFACTURER") "Kyocera AVX")
        (field (name "TOLERANCE") "20%")
        (field (name "VOLTAGE RATING (DC)") "6.3V")
        (field (name "CAPACITANCE") "1uF")
        (field (name "CASE/PACKAGE") "0201")
      )
      (libsource (lib "Electronic Devices_LIB") (part "CAP_1UF_6.3V_X5R_0201"))
    )
    (comp (ref "C157")
      (value "0201X104K100CT")
      (footprint "CAP_0201_CAPC0603X03N")
      (description "0201 0.1 uF 10 V ±10 %Tolerance X5R Surface Mount Multilayer Ceramic Capacitor")
      (fields
        (field (name "MANUFACTURER") "Walsin Technologies")
        (field (name "TOLERANCE") "10%")
        (field (name "CAPACITANCE") "100nF")
        (field (name "VOLTAGE RATING") "10V")
        (field (name "CASE/PACKAGE") "0201")
      )
      (libsource (lib "Electronic Devices_LIB") (part "CAP_0.1UF_10V_X5R_0201"))
    )
    (comp (ref "C158")
      (value "C1005X5R1A225K050BC")
      (footprint "CAP_0201_CAPC0603X03N")
      (description "Multilayer Ceramic Capacitor, 2.2 uF, 10 V, ± 10%, X5R, 0402 [1005 Metric]")
      (fields
        (field (name "MANUFACTURER") "TDK")
        (field (name "TOLERANCE") "10%")
        (field (name "VOLTAGE RATING (DC)") "10V")
        (field (name "CAPACITANCE") "2.2uF")
        (field (name "CASE/PACKAGE") "0402")
      )
      (libsource (lib "Electronic Devices_LIB") (part "CAP_2.2UF_10V_X5R_0402"))
    )
    (comp (ref "C159")
      (value "C1608X5R1A226M080AC")
      (footprint "CAP_0603_CAPC1608X08N")
      (description "Multilayer Ceramic Capacitor, 22 uF, 10 V, ± 20%, X5R, 0603 [1608 Metric]")
      (fields
        (field (name "MANUFACTURER") "TDK")
        (field (name "TOLERANCE") "20%")
        (field (name "CAPACITANCE") "22uF")
        (field (name "VOLTAGE RATING") "10V")
        (field (name "CASE CODE (IMPERIAL)") "0603")
      )
      (libsource (lib "Electronic Devices_LIB") (part "CAP_22UF_10V_X5R_0603"))
    )
    (comp (ref "C160")
      (value "C1608X5R1A226M080AC")
      (footprint "CAP_0603_CAPC1608X08N")
      (description "Multilayer Ceramic Capacitor, 22 uF, 10 V, ± 20%, X5R, 0603 [1608 Metric]")
      (fields
        (field (name "MANUFACTURER") "TDK")
        (field (name "TOLERANCE") "20%")
        (field (name "CAPACITANCE") "22uF")
        (field (name "VOLTAGE RATING") "10V")
        (field (name "CASE CODE (IMPERIAL)") "0603")
      )
      (libsource (lib "Electronic Devices_LIB") (part "CAP_22UF_10V_X5R_0603"))
    )
    (comp (ref "C161")
      (value "02016D105MAT2A")
      (footprint "CAP_0201_CAPC0603X03N")
      (description "0201 1 uF 6.3 V ±20 % Tolerance X5R Surface Mount Multilayer Ceramic Capacitor")
      (fields
        (field (name "MANUFACTURER") "Kyocera AVX")
        (field (name "TOLERANCE") "20%")
        (field (name "VOLTAGE RATING (DC)") "6.3V")
        (field (name "CAPACITANCE") "1uF")
        (field (name "CASE/PACKAGE") "0201")
      )
      (libsource (lib "Electronic Devices_LIB") (part "CAP_1UF_6.3V_X5R_0201"))
    )
    (comp (ref "C162")
      (value "02016D105MAT2A")
      (footprint "CAP_0201_CAPC0603X03N")
      (description "0201 1 uF 6.3 V ±20 % Tolerance X5R Surface Mount Multilayer Ceramic Capacitor")
      (fields
        (field (name "MANUFACTURER") "Kyocera AVX")
        (field (name "TOLERANCE") "20%")
        (field (name "VOLTAGE RATING (DC)") "6.3V")
        (field (name "CAPACITANCE") "1uF")
        (field (name "CASE/PACKAGE") "0201")
      )
      (libsource (lib "Electronic Devices_LIB") (part "CAP_1UF_6.3V_X5R_0201"))
    )
    (comp (ref "C163")
      (value "02016D105MAT2A")
      (footprint "CAP_0201_CAPC0603X03N")
      (description "0201 1 uF 6.3 V ±20 % Tolerance X5R Surface Mount Multilayer Ceramic Capacitor")
      (fields
        (field (name "MANUFACTURER") "Kyocera AVX")
        (field (name "TOLERANCE") "20%")
        (field (name "VOLTAGE RATING (DC)") "6.3V")
        (field (name "CAPACITANCE") "1uF")
        (field (name "CASE/PACKAGE") "0201")
      )
      (libsource (lib "Electronic Devices_LIB") (part "CAP_1UF_6.3V_X5R_0201"))
    )
    (comp (ref "C164")
      (value "02016D105MAT2A")
      (footprint "CAP_0201_CAPC0603X03N")
      (description "0201 1 uF 6.3 V ±20 % Tolerance X5R Surface Mount Multilayer Ceramic Capacitor")
      (fields
        (field (name "MANUFACTURER") "Kyocera AVX")
        (field (name "TOLERANCE") "20%")
        (field (name "VOLTAGE RATING (DC)") "6.3V")
        (field (name "CAPACITANCE") "1uF")
        (field (name "CASE/PACKAGE") "0201")
      )
      (libsource (lib "Electronic Devices_LIB") (part "CAP_1UF_6.3V_X5R_0201"))
    )
    (comp (ref "C165")
      (value "C0402C103K8RACTU")
      (footprint "CAP_0402_CAPC1005X05N")
      (description "Ceramic Capacitor, Multilayer, Ceramic, 10V, 10% +Tol, 10% -Tol, X7R, 15% TC, 0.01uF, 0402")
      (fields
        (field (name "MANUFACTURER") "KEMET")
        (field (name "TOLERANCE") "10%")
        (field (name "CASE CODE (IMPERIAL)") "0402")
        (field (name "VOLTAGE RATING") "10V")
        (field (name "CAPACITANCE") "10nF")
      )
      (libsource (lib "Electronic Devices_LIB") (part "CAP_10nF_10V_X7R_0402"))
    )
    (comp (ref "C166")
      (value "C0402C103K8RACTU")
      (footprint "CAP_0402_CAPC1005X05N")
      (description "Ceramic Capacitor, Multilayer, Ceramic, 10V, 10% +Tol, 10% -Tol, X7R, 15% TC, 0.01uF, 0402")
      (fields
        (field (name "MANUFACTURER") "KEMET")
        (field (name "TOLERANCE") "10%")
        (field (name "CASE CODE (IMPERIAL)") "0402")
        (field (name "VOLTAGE RATING") "10V")
        (field (name "CAPACITANCE") "10nF")
      )
      (libsource (lib "Electronic Devices_LIB") (part "CAP_10nF_10V_X7R_0402"))
    )
    (comp (ref "C167")
      (value "GRM033R61A472KA01D")
      (footprint "CAP_0201_CAPC0603X03N")
      (description "Multilayer Ceramic Capacitor, 4700 pF, 10 V, ± 10%, X5R, 0201 [0603 Metric]")
      (fields
        (field (name "MANUFACTURER") "Murata")
        (field (name "TOLERANCE") "10%")
        (field (name "VOLTAGE RATING") "10V")
        (field (name "CAPACITANCE") "4.7nF")
        (field (name "CASE/PACKAGE") "0201")
      )
      (libsource (lib "Electronic Devices_LIB") (part "CAP_4700pF_10V_0201"))
    )
    (comp (ref "C168")
      (value "GRM033R61A472KA01D")
      (footprint "CAP_0201_CAPC0603X03N")
      (description "Multilayer Ceramic Capacitor, 4700 pF, 10 V, ± 10%, X5R, 0201 [0603 Metric]")
      (fields
        (field (name "MANUFACTURER") "Murata")
        (field (name "TOLERANCE") "10%")
        (field (name "VOLTAGE RATING") "10V")
        (field (name "CAPACITANCE") "4.7nF")
        (field (name "CASE/PACKAGE") "0201")
      )
      (libsource (lib "Electronic Devices_LIB") (part "CAP_4700pF_10V_0201"))
    )
    (comp (ref "C169")
      (value "0201X104K100CT")
      (footprint "CAP_0201_CAPC0603X03N")
      (description "0201 0.1 uF 10 V ±10 %Tolerance X5R Surface Mount Multilayer Ceramic Capacitor")
      (fields
        (field (name "MANUFACTURER") "Walsin Technologies")
        (field (name "TOLERANCE") "10%")
        (field (name "CAPACITANCE") "100nF")
        (field (name "VOLTAGE RATING") "10V")
        (field (name "CASE/PACKAGE") "0201")
      )
      (libsource (lib "Electronic Devices_LIB") (part "CAP_0.1UF_10V_X5R_0201"))
    )
    (comp (ref "C170")
      (value "0201X104K100CT")
      (footprint "CAP_0201_CAPC0603X03N")
      (description "0201 0.1 uF 10 V ±10 %Tolerance X5R Surface Mount Multilayer Ceramic Capacitor")
      (fields
        (field (name "MANUFACTURER") "Walsin Technologies")
        (field (name "TOLERANCE") "10%")
        (field (name "CAPACITANCE") "100nF")
        (field (name "VOLTAGE RATING") "10V")
        (field (name "CASE/PACKAGE") "0201")
      )
      (libsource (lib "Electronic Devices_LIB") (part "CAP_0.1UF_10V_X5R_0201"))
    )
    (comp (ref "C171")
      (value "0201X104K100CT")
      (footprint "CAP_0201_CAPC0603X03N")
      (description "0201 0.1 uF 10 V ±10 %Tolerance X5R Surface Mount Multilayer Ceramic Capacitor")
      (fields
        (field (name "MANUFACTURER") "Walsin Technologies")
        (field (name "TOLERANCE") "10%")
        (field (name "CAPACITANCE") "100nF")
        (field (name "VOLTAGE RATING") "10V")
        (field (name "CASE/PACKAGE") "0201")
      )
      (libsource (lib "Electronic Devices_LIB") (part "CAP_0.1UF_10V_X5R_0201"))
    )
    (comp (ref "C172")
      (value "C1005X5R1A225K050BC")
      (footprint "CAP_0201_CAPC0603X03N")
      (description "Multilayer Ceramic Capacitor, 2.2 uF, 10 V, ± 10%, X5R, 0402 [1005 Metric]")
      (fields
        (field (name "MANUFACTURER") "TDK")
        (field (name "TOLERANCE") "10%")
        (field (name "VOLTAGE RATING (DC)") "10V")
        (field (name "CAPACITANCE") "2.2uF")
        (field (name "CASE/PACKAGE") "0402")
      )
      (libsource (lib "Electronic Devices_LIB") (part "CAP_2.2UF_10V_X5R_0402"))
    )
    (comp (ref "C173")
      (value "0201X104K100CT")
      (footprint "CAP_0201_CAPC0603X03N")
      (description "0201 0.1 uF 10 V ±10 %Tolerance X5R Surface Mount Multilayer Ceramic Capacitor")
      (fields
        (field (name "MANUFACTURER") "Walsin Technologies")
        (field (name "TOLERANCE") "10%")
        (field (name "CAPACITANCE") "100nF")
        (field (name "VOLTAGE RATING") "10V")
        (field (name "CASE/PACKAGE") "0201")
      )
      (libsource (lib "Electronic Devices_LIB") (part "CAP_0.1UF_10V_X5R_0201"))
    )
    (comp (ref "C174")
      (value "0201X104K100CT")
      (footprint "CAP_0201_CAPC0603X03N")
      (description "0201 0.1 uF 10 V ±10 %Tolerance X5R Surface Mount Multilayer Ceramic Capacitor")
      (fields
        (field (name "MANUFACTURER") "Walsin Technologies")
        (field (name "TOLERANCE") "10%")
        (field (name "CAPACITANCE") "100nF")
        (field (name "VOLTAGE RATING") "10V")
        (field (name "CASE/PACKAGE") "0201")
      )
      (libsource (lib "Electronic Devices_LIB") (part "CAP_0.1UF_10V_X5R_0201"))
    )
    (comp (ref "C175")
      (value "C1608X5R1A226M080AC")
      (footprint "CAP_0603_CAPC1608X08N")
      (description "Multilayer Ceramic Capacitor, 22 uF, 10 V, ± 20%, X5R, 0603 [1608 Metric]")
      (fields
        (field (name "MANUFACTURER") "TDK")
        (field (name "TOLERANCE") "20%")
        (field (name "CAPACITANCE") "22uF")
        (field (name "VOLTAGE RATING") "10V")
        (field (name "CASE CODE (IMPERIAL)") "0603")
      )
      (libsource (lib "Electronic Devices_LIB") (part "CAP_22UF_10V_X5R_0603"))
    )
    (comp (ref "C176")
      (value "GRM033R61A472KA01D")
      (footprint "CAP_0201_CAPC0603X03N")
      (description "Multilayer Ceramic Capacitor, 4700 pF, 10 V, ± 10%, X5R, 0201 [0603 Metric]")
      (fields
        (field (name "MANUFACTURER") "Murata")
        (field (name "TOLERANCE") "10%")
        (field (name "VOLTAGE RATING") "10V")
        (field (name "CAPACITANCE") "4.7nF")
        (field (name "CASE/PACKAGE") "0201")
      )
      (libsource (lib "Electronic Devices_LIB") (part "CAP_4700pF_10V_0201"))
    )
    (comp (ref "C177")
      (value "GRM033R61A472KA01D")
      (footprint "CAP_0201_CAPC0603X03N")
      (description "Multilayer Ceramic Capacitor, 4700 pF, 10 V, ± 10%, X5R, 0201 [0603 Metric]")
      (fields
        (field (name "MANUFACTURER") "Murata")
        (field (name "TOLERANCE") "10%")
        (field (name "VOLTAGE RATING") "10V")
        (field (name "CAPACITANCE") "4.7nF")
        (field (name "CASE/PACKAGE") "0201")
      )
      (libsource (lib "Electronic Devices_LIB") (part "CAP_4700pF_10V_0201"))
    )
    (comp (ref "C178")
      (value "GRM033R61A472KA01D")
      (footprint "CAP_0201_CAPC0603X03N")
      (description "Multilayer Ceramic Capacitor, 4700 pF, 10 V, ± 10%, X5R, 0201 [0603 Metric]")
      (fields
        (field (name "MANUFACTURER") "Murata")
        (field (name "TOLERANCE") "10%")
        (field (name "VOLTAGE RATING") "10V")
        (field (name "CAPACITANCE") "4.7nF")
        (field (name "CASE/PACKAGE") "0201")
      )
      (libsource (lib "Electronic Devices_LIB") (part "CAP_4700pF_10V_0201"))
    )
    (comp (ref "C179")
      (value "GRM033R61A472KA01D")
      (footprint "CAP_0201_CAPC0603X03N")
      (description "Multilayer Ceramic Capacitor, 4700 pF, 10 V, ± 10%, X5R, 0201 [0603 Metric]")
      (fields
        (field (name "MANUFACTURER") "Murata")
        (field (name "TOLERANCE") "10%")
        (field (name "VOLTAGE RATING") "10V")
        (field (name "CAPACITANCE") "4.7nF")
        (field (name "CASE/PACKAGE") "0201")
      )
      (libsource (lib "Electronic Devices_LIB") (part "CAP_4700pF_10V_0201"))
    )
    (comp (ref "C180")
      (value "GRM033R61A472KA01D")
      (footprint "CAP_0201_CAPC0603X03N")
      (description "Multilayer Ceramic Capacitor, 4700 pF, 10 V, ± 10%, X5R, 0201 [0603 Metric]")
      (fields
        (field (name "MANUFACTURER") "Murata")
        (field (name "TOLERANCE") "10%")
        (field (name "VOLTAGE RATING") "10V")
        (field (name "CAPACITANCE") "4.7nF")
        (field (name "CASE/PACKAGE") "0201")
      )
      (libsource (lib "Electronic Devices_LIB") (part "CAP_4700pF_10V_0201"))
    )
    (comp (ref "C181")
      (value "GRM033R61A472KA01D")
      (footprint "CAP_0201_CAPC0603X03N")
      (description "Multilayer Ceramic Capacitor, 4700 pF, 10 V, ± 10%, X5R, 0201 [0603 Metric]")
      (fields
        (field (name "MANUFACTURER") "Murata")
        (field (name "TOLERANCE") "10%")
        (field (name "VOLTAGE RATING") "10V")
        (field (name "CAPACITANCE") "4.7nF")
        (field (name "CASE/PACKAGE") "0201")
      )
      (libsource (lib "Electronic Devices_LIB") (part "CAP_4700pF_10V_0201"))
    )
    (comp (ref "C182")
      (value "GRM033R61A472KA01D")
      (footprint "CAP_0201_CAPC0603X03N")
      (description "Multilayer Ceramic Capacitor, 4700 pF, 10 V, ± 10%, X5R, 0201 [0603 Metric]")
      (fields
        (field (name "MANUFACTURER") "Murata")
        (field (name "TOLERANCE") "10%")
        (field (name "VOLTAGE RATING") "10V")
        (field (name "CAPACITANCE") "4.7nF")
        (field (name "CASE/PACKAGE") "0201")
      )
      (libsource (lib "Electronic Devices_LIB") (part "CAP_4700pF_10V_0201"))
    )
    (comp (ref "C183")
      (value "GRM033R61A472KA01D")
      (footprint "CAP_0201_CAPC0603X03N")
      (description "Multilayer Ceramic Capacitor, 4700 pF, 10 V, ± 10%, X5R, 0201 [0603 Metric]")
      (fields
        (field (name "MANUFACTURER") "Murata")
        (field (name "TOLERANCE") "10%")
        (field (name "VOLTAGE RATING") "10V")
        (field (name "CAPACITANCE") "4.7nF")
        (field (name "CASE/PACKAGE") "0201")
      )
      (libsource (lib "Electronic Devices_LIB") (part "CAP_4700pF_10V_0201"))
    )
    (comp (ref "C184")
      (value "GRM033R61A472KA01D")
      (footprint "CAP_0201_CAPC0603X03N")
      (description "Multilayer Ceramic Capacitor, 4700 pF, 10 V, ± 10%, X5R, 0201 [0603 Metric]")
      (fields
        (field (name "MANUFACTURER") "Murata")
        (field (name "TOLERANCE") "10%")
        (field (name "VOLTAGE RATING") "10V")
        (field (name "CAPACITANCE") "4.7nF")
        (field (name "CASE/PACKAGE") "0201")
      )
      (libsource (lib "Electronic Devices_LIB") (part "CAP_4700pF_10V_0201"))
    )
    (comp (ref "C185")
      (value "C1608X5R1A226M080AC")
      (footprint "CAP_0603_CAPC1608X08N")
      (description "Multilayer Ceramic Capacitor, 22 uF, 10 V, ± 20%, X5R, 0603 [1608 Metric]")
      (fields
        (field (name "MANUFACTURER") "TDK")
        (field (name "TOLERANCE") "20%")
        (field (name "CAPACITANCE") "22uF")
        (field (name "VOLTAGE RATING") "10V")
        (field (name "CASE CODE (IMPERIAL)") "0603")
      )
      (libsource (lib "Electronic Devices_LIB") (part "CAP_22UF_10V_X5R_0603"))
    )
    (comp (ref "C186")
      (value "0201X104K100CT")
      (footprint "CAP_0201_CAPC0603X03N")
      (description "0201 0.1 uF 10 V ±10 %Tolerance X5R Surface Mount Multilayer Ceramic Capacitor")
      (fields
        (field (name "MANUFACTURER") "Walsin Technologies")
        (field (name "TOLERANCE") "10%")
        (field (name "CAPACITANCE") "100nF")
        (field (name "VOLTAGE RATING") "10V")
        (field (name "CASE/PACKAGE") "0201")
      )
      (libsource (lib "Electronic Devices_LIB") (part "CAP_0.1UF_10V_X5R_0201"))
    )
    (comp (ref "C187")
      (value "0201X104K100CT")
      (footprint "CAP_0201_CAPC0603X03N")
      (description "0201 0.1 uF 10 V ±10 %Tolerance X5R Surface Mount Multilayer Ceramic Capacitor")
      (fields
        (field (name "MANUFACTURER") "Walsin Technologies")
        (field (name "TOLERANCE") "10%")
        (field (name "CAPACITANCE") "100nF")
        (field (name "VOLTAGE RATING") "10V")
        (field (name "CASE/PACKAGE") "0201")
      )
      (libsource (lib "Electronic Devices_LIB") (part "CAP_0.1UF_10V_X5R_0201"))
    )
    (comp (ref "C188")
      (value "0201X104K100CT")
      (footprint "CAP_0201_CAPC0603X03N")
      (description "0201 0.1 uF 10 V ±10 %Tolerance X5R Surface Mount Multilayer Ceramic Capacitor")
      (fields
        (field (name "MANUFACTURER") "Walsin Technologies")
        (field (name "TOLERANCE") "10%")
        (field (name "CAPACITANCE") "100nF")
        (field (name "VOLTAGE RATING") "10V")
        (field (name "CASE/PACKAGE") "0201")
      )
      (libsource (lib "Electronic Devices_LIB") (part "CAP_0.1UF_10V_X5R_0201"))
    )
    (comp (ref "C189")
      (value "0201X104K100CT")
      (footprint "CAP_0201_CAPC0603X03N")
      (description "0201 0.1 uF 10 V ±10 %Tolerance X5R Surface Mount Multilayer Ceramic Capacitor")
      (fields
        (field (name "MANUFACTURER") "Walsin Technologies")
        (field (name "TOLERANCE") "10%")
        (field (name "CAPACITANCE") "100nF")
        (field (name "VOLTAGE RATING") "10V")
        (field (name "CASE/PACKAGE") "0201")
      )
      (libsource (lib "Electronic Devices_LIB") (part "CAP_0.1UF_10V_X5R_0201"))
    )
    (comp (ref "C190")
      (value "0201X104K100CT")
      (footprint "CAP_0201_CAPC0603X03N")
      (description "0201 0.1 uF 10 V ±10 %Tolerance X5R Surface Mount Multilayer Ceramic Capacitor")
      (fields
        (field (name "MANUFACTURER") "Walsin Technologies")
        (field (name "TOLERANCE") "10%")
        (field (name "CAPACITANCE") "100nF")
        (field (name "VOLTAGE RATING") "10V")
        (field (name "CASE/PACKAGE") "0201")
      )
      (libsource (lib "Electronic Devices_LIB") (part "CAP_0.1UF_10V_X5R_0201"))
    )
    (comp (ref "C191")
      (value "0201X104K100CT")
      (footprint "CAP_0201_CAPC0603X03N")
      (description "0201 0.1 uF 10 V ±10 %Tolerance X5R Surface Mount Multilayer Ceramic Capacitor")
      (fields
        (field (name "MANUFACTURER") "Walsin Technologies")
        (field (name "TOLERANCE") "10%")
        (field (name "CAPACITANCE") "100nF")
        (field (name "VOLTAGE RATING") "10V")
        (field (name "CASE/PACKAGE") "0201")
      )
      (libsource (lib "Electronic Devices_LIB") (part "CAP_0.1UF_10V_X5R_0201"))
    )
    (comp (ref "C192")
      (value "C1608X5R1A226M080AC")
      (footprint "CAP_0603_CAPC1608X08N")
      (description "Multilayer Ceramic Capacitor, 22 uF, 10 V, ± 20%, X5R, 0603 [1608 Metric]")
      (fields
        (field (name "MANUFACTURER") "TDK")
        (field (name "TOLERANCE") "20%")
        (field (name "CAPACITANCE") "22uF")
        (field (name "VOLTAGE RATING") "10V")
        (field (name "CASE CODE (IMPERIAL)") "0603")
      )
      (libsource (lib "Electronic Devices_LIB") (part "CAP_22UF_10V_X5R_0603"))
    )
    (comp (ref "C193")
      (value "C1608X5R1A226M080AC")
      (footprint "CAP_0603_CAPC1608X08N")
      (description "Multilayer Ceramic Capacitor, 22 uF, 10 V, ± 20%, X5R, 0603 [1608 Metric]")
      (fields
        (field (name "MANUFACTURER") "TDK")
        (field (name "TOLERANCE") "20%")
        (field (name "CAPACITANCE") "22uF")
        (field (name "VOLTAGE RATING") "10V")
        (field (name "CASE CODE (IMPERIAL)") "0603")
      )
      (libsource (lib "Electronic Devices_LIB") (part "CAP_22UF_10V_X5R_0603"))
    )
    (comp (ref "C194")
      (value "02016D105MAT2A")
      (footprint "CAP_0201_CAPC0603X03N")
      (description "0201 1 uF 6.3 V ±20 % Tolerance X5R Surface Mount Multilayer Ceramic Capacitor")
      (fields
        (field (name "MANUFACTURER") "Kyocera AVX")
        (field (name "TOLERANCE") "20%")
        (field (name "VOLTAGE RATING (DC)") "6.3V")
        (field (name "CAPACITANCE") "1uF")
        (field (name "CASE/PACKAGE") "0201")
      )
      (libsource (lib "Electronic Devices_LIB") (part "CAP_1UF_6.3V_X5R_0201"))
    )
    (comp (ref "C195")
      (value "02016D105MAT2A")
      (footprint "CAP_0201_CAPC0603X03N")
      (description "0201 1 uF 6.3 V ±20 % Tolerance X5R Surface Mount Multilayer Ceramic Capacitor")
      (fields
        (field (name "MANUFACTURER") "Kyocera AVX")
        (field (name "TOLERANCE") "20%")
        (field (name "VOLTAGE RATING (DC)") "6.3V")
        (field (name "CAPACITANCE") "1uF")
        (field (name "CASE/PACKAGE") "0201")
      )
      (libsource (lib "Electronic Devices_LIB") (part "CAP_1UF_6.3V_X5R_0201"))
    )
    (comp (ref "C196")
      (value "02016D105MAT2A")
      (footprint "CAP_0201_CAPC0603X03N")
      (description "0201 1 uF 6.3 V ±20 % Tolerance X5R Surface Mount Multilayer Ceramic Capacitor")
      (fields
        (field (name "MANUFACTURER") "Kyocera AVX")
        (field (name "TOLERANCE") "20%")
        (field (name "VOLTAGE RATING (DC)") "6.3V")
        (field (name "CAPACITANCE") "1uF")
        (field (name "CASE/PACKAGE") "0201")
      )
      (libsource (lib "Electronic Devices_LIB") (part "CAP_1UF_6.3V_X5R_0201"))
    )
    (comp (ref "C197")
      (value "02016D105MAT2A")
      (footprint "CAP_0201_CAPC0603X03N")
      (description "0201 1 uF 6.3 V ±20 % Tolerance X5R Surface Mount Multilayer Ceramic Capacitor")
      (fields
        (field (name "MANUFACTURER") "Kyocera AVX")
        (field (name "TOLERANCE") "20%")
        (field (name "VOLTAGE RATING (DC)") "6.3V")
        (field (name "CAPACITANCE") "1uF")
        (field (name "CASE/PACKAGE") "0201")
      )
      (libsource (lib "Electronic Devices_LIB") (part "CAP_1UF_6.3V_X5R_0201"))
    )
    (comp (ref "C198")
      (value "02016D105MAT2A")
      (footprint "CAP_0201_CAPC0603X03N")
      (description "0201 1 uF 6.3 V ±20 % Tolerance X5R Surface Mount Multilayer Ceramic Capacitor")
      (fields
        (field (name "MANUFACTURER") "Kyocera AVX")
        (field (name "TOLERANCE") "20%")
        (field (name "VOLTAGE RATING (DC)") "6.3V")
        (field (name "CAPACITANCE") "1uF")
        (field (name "CASE/PACKAGE") "0201")
      )
      (libsource (lib "Electronic Devices_LIB") (part "CAP_1UF_6.3V_X5R_0201"))
    )
    (comp (ref "C199")
      (value "02016D105MAT2A")
      (footprint "CAP_0201_CAPC0603X03N")
      (description "0201 1 uF 6.3 V ±20 % Tolerance X5R Surface Mount Multilayer Ceramic Capacitor")
      (fields
        (field (name "MANUFACTURER") "Kyocera AVX")
        (field (name "TOLERANCE") "20%")
        (field (name "VOLTAGE RATING (DC)") "6.3V")
        (field (name "CAPACITANCE") "1uF")
        (field (name "CASE/PACKAGE") "0201")
      )
      (libsource (lib "Electronic Devices_LIB") (part "CAP_1UF_6.3V_X5R_0201"))
    )
    (comp (ref "C200")
      (value "02016D105MAT2A")
      (footprint "CAP_0201_CAPC0603X03N")
      (description "0201 1 uF 6.3 V ±20 % Tolerance X5R Surface Mount Multilayer Ceramic Capacitor")
      (fields
        (field (name "MANUFACTURER") "Kyocera AVX")
        (field (name "TOLERANCE") "20%")
        (field (name "VOLTAGE RATING (DC)") "6.3V")
        (field (name "CAPACITANCE") "1uF")
        (field (name "CASE/PACKAGE") "0201")
      )
      (libsource (lib "Electronic Devices_LIB") (part "CAP_1UF_6.3V_X5R_0201"))
    )
    (comp (ref "C201")
      (value "02016D105MAT2A")
      (footprint "CAP_0201_CAPC0603X03N")
      (description "0201 1 uF 6.3 V ±20 % Tolerance X5R Surface Mount Multilayer Ceramic Capacitor")
      (fields
        (field (name "MANUFACTURER") "Kyocera AVX")
        (field (name "TOLERANCE") "20%")
        (field (name "VOLTAGE RATING (DC)") "6.3V")
        (field (name "CAPACITANCE") "1uF")
        (field (name "CASE/PACKAGE") "0201")
      )
      (libsource (lib "Electronic Devices_LIB") (part "CAP_1UF_6.3V_X5R_0201"))
    )
    (comp (ref "C202")
      (value "C1608X5R1A226M080AC")
      (footprint "CAP_0603_CAPC1608X08N")
      (description "Multilayer Ceramic Capacitor, 22 uF, 10 V, ± 20%, X5R, 0603 [1608 Metric]")
      (fields
        (field (name "MANUFACTURER") "TDK")
        (field (name "TOLERANCE") "20%")
        (field (name "CAPACITANCE") "22uF")
        (field (name "VOLTAGE RATING") "10V")
        (field (name "CASE CODE (IMPERIAL)") "0603")
      )
      (libsource (lib "Electronic Devices_LIB") (part "CAP_22UF_10V_X5R_0603"))
    )
    (comp (ref "C203")
      (value "02016D105MAT2A")
      (footprint "CAP_0201_CAPC0603X03N")
      (description "0201 1 uF 6.3 V ±20 % Tolerance X5R Surface Mount Multilayer Ceramic Capacitor")
      (fields
        (field (name "MANUFACTURER") "Kyocera AVX")
        (field (name "TOLERANCE") "20%")
        (field (name "VOLTAGE RATING (DC)") "6.3V")
        (field (name "CAPACITANCE") "1uF")
        (field (name "CASE/PACKAGE") "0201")
      )
      (libsource (lib "Electronic Devices_LIB") (part "CAP_1UF_6.3V_X5R_0201"))
    )
    (comp (ref "C204")
      (value "02016D105MAT2A")
      (footprint "CAP_0201_CAPC0603X03N")
      (description "0201 1 uF 6.3 V ±20 % Tolerance X5R Surface Mount Multilayer Ceramic Capacitor")
      (fields
        (field (name "MANUFACTURER") "Kyocera AVX")
        (field (name "TOLERANCE") "20%")
        (field (name "VOLTAGE RATING (DC)") "6.3V")
        (field (name "CAPACITANCE") "1uF")
        (field (name "CASE/PACKAGE") "0201")
      )
      (libsource (lib "Electronic Devices_LIB") (part "CAP_1UF_6.3V_X5R_0201"))
    )
    (comp (ref "C205")
      (value "02016D105MAT2A")
      (footprint "CAP_0201_CAPC0603X03N")
      (description "0201 1 uF 6.3 V ±20 % Tolerance X5R Surface Mount Multilayer Ceramic Capacitor")
      (fields
        (field (name "MANUFACTURER") "Kyocera AVX")
        (field (name "TOLERANCE") "20%")
        (field (name "VOLTAGE RATING (DC)") "6.3V")
        (field (name "CAPACITANCE") "1uF")
        (field (name "CASE/PACKAGE") "0201")
      )
      (libsource (lib "Electronic Devices_LIB") (part "CAP_1UF_6.3V_X5R_0201"))
    )
    (comp (ref "C206")
      (value "02016D105MAT2A")
      (footprint "CAP_0201_CAPC0603X03N")
      (description "0201 1 uF 6.3 V ±20 % Tolerance X5R Surface Mount Multilayer Ceramic Capacitor")
      (fields
        (field (name "MANUFACTURER") "Kyocera AVX")
        (field (name "TOLERANCE") "20%")
        (field (name "VOLTAGE RATING (DC)") "6.3V")
        (field (name "CAPACITANCE") "1uF")
        (field (name "CASE/PACKAGE") "0201")
      )
      (libsource (lib "Electronic Devices_LIB") (part "CAP_1UF_6.3V_X5R_0201"))
    )
    (comp (ref "C207")
      (value "02016D105MAT2A")
      (footprint "CAP_0201_CAPC0603X03N")
      (description "0201 1 uF 6.3 V ±20 % Tolerance X5R Surface Mount Multilayer Ceramic Capacitor")
      (fields
        (field (name "MANUFACTURER") "Kyocera AVX")
        (field (name "TOLERANCE") "20%")
        (field (name "VOLTAGE RATING (DC)") "6.3V")
        (field (name "CAPACITANCE") "1uF")
        (field (name "CASE/PACKAGE") "0201")
      )
      (libsource (lib "Electronic Devices_LIB") (part "CAP_1UF_6.3V_X5R_0201"))
    )
    (comp (ref "C208")
      (value "02016D105MAT2A")
      (footprint "CAP_0201_CAPC0603X03N")
      (description "0201 1 uF 6.3 V ±20 % Tolerance X5R Surface Mount Multilayer Ceramic Capacitor")
      (fields
        (field (name "MANUFACTURER") "Kyocera AVX")
        (field (name "TOLERANCE") "20%")
        (field (name "VOLTAGE RATING (DC)") "6.3V")
        (field (name "CAPACITANCE") "1uF")
        (field (name "CASE/PACKAGE") "0201")
      )
      (libsource (lib "Electronic Devices_LIB") (part "CAP_1UF_6.3V_X5R_0201"))
    )
    (comp (ref "C209")
      (value "02016D105MAT2A")
      (footprint "CAP_0201_CAPC0603X03N")
      (description "0201 1 uF 6.3 V ±20 % Tolerance X5R Surface Mount Multilayer Ceramic Capacitor")
      (fields
        (field (name "MANUFACTURER") "Kyocera AVX")
        (field (name "TOLERANCE") "20%")
        (field (name "VOLTAGE RATING (DC)") "6.3V")
        (field (name "CAPACITANCE") "1uF")
        (field (name "CASE/PACKAGE") "0201")
      )
      (libsource (lib "Electronic Devices_LIB") (part "CAP_1UF_6.3V_X5R_0201"))
    )
    (comp (ref "C210")
      (value "02016D105MAT2A")
      (footprint "CAP_0201_CAPC0603X03N")
      (description "0201 1 uF 6.3 V ±20 % Tolerance X5R Surface Mount Multilayer Ceramic Capacitor")
      (fields
        (field (name "MANUFACTURER") "Kyocera AVX")
        (field (name "TOLERANCE") "20%")
        (field (name "VOLTAGE RATING (DC)") "6.3V")
        (field (name "CAPACITANCE") "1uF")
        (field (name "CASE/PACKAGE") "0201")
      )
      (libsource (lib "Electronic Devices_LIB") (part "CAP_1UF_6.3V_X5R_0201"))
    )
    (comp (ref "C211")
      (value "02016D105MAT2A")
      (footprint "CAP_0201_CAPC0603X03N")
      (description "0201 1 uF 6.3 V ±20 % Tolerance X5R Surface Mount Multilayer Ceramic Capacitor")
      (fields
        (field (name "MANUFACTURER") "Kyocera AVX")
        (field (name "TOLERANCE") "20%")
        (field (name "VOLTAGE RATING (DC)") "6.3V")
        (field (name "CAPACITANCE") "1uF")
        (field (name "CASE/PACKAGE") "0201")
      )
      (libsource (lib "Electronic Devices_LIB") (part "CAP_1UF_6.3V_X5R_0201"))
    )
    (comp (ref "C212")
      (value "02016D105MAT2A")
      (footprint "CAP_0201_CAPC0603X03N")
      (description "0201 1 uF 6.3 V ±20 % Tolerance X5R Surface Mount Multilayer Ceramic Capacitor")
      (fields
        (field (name "MANUFACTURER") "Kyocera AVX")
        (field (name "TOLERANCE") "20%")
        (field (name "VOLTAGE RATING (DC)") "6.3V")
        (field (name "CAPACITANCE") "1uF")
        (field (name "CASE/PACKAGE") "0201")
      )
      (libsource (lib "Electronic Devices_LIB") (part "CAP_1UF_6.3V_X5R_0201"))
    )
    (comp (ref "L9")
      (value "BLM03AX241SN1D")
      (footprint "IND_0201_FERRITE_BEAD")
      (description "Ferrite Beads Multi-Layer 240Ohm 25% 100MHz 350mA 380mOhm DCR 0201 Paper T/R")
      (fields
        (field (name "MANUFACTURER") "Murata")
        (field (name "TOLERANCE") "25%")
        (field (name "IMPEDANCE") "240R")
        (field (name "CASE/PACKAGE") "0201")
      )
      (libsource (lib "Electronic Devices_LIB") (part "IND_FERRITE_BEADS_350mA_0201_BLM03AX241SN1D"))
    )
    (comp (ref "L10")
      (value "BLM18PG121SH1D")
      (footprint "IND_0603_INDC1608X08N")
      (description "Ferrite Beads Multi-Layer 120Ohm 25% 100MHz 2A 50mOhm DCR 0603 Automotive Paper T/R")
      (fields
        (field (name "MANUFACTURER") "Murata")
        (field (name "TOLERANCE") "25%")
        (field (name "IMPEDANCE") "120R")
        (field (name "CASE/PACKAGE") "0603")
      )
      (libsource (lib "Electronic Devices_LIB") (part "IND_FERRITE_BEADS_120R_2A_0603_BLM18PG121SH1D"))
    )
    (comp (ref "R41")
      (value "ERJ-2GE0R00X")
      (footprint "RES_0402_RESC1005X04N")
      (description "SMD Chip Resistor, Jumper, 0 ohm, 100 mW, 0402 [1005 Metric], Thick Film, General Purpose")
      (fields
        (field (name "MANUFACTURER") "Panasonic")
        (field (name "CASE CODE (IMPERIAL)") "0402")
        (field (name "TOLERANCE") "5%")
        (field (name "RESISTANCE") "0R")
      )
      (libsource (lib "Electronic Devices_LIB") (part "RES_0R_5%_100mW_0402"))
    )
    (comp (ref "R42")
      (value "ERJ-2GE0R00X")
      (footprint "RES_0402_RESC1005X04N")
      (description "SMD Chip Resistor, Jumper, 0 ohm, 100 mW, 0402 [1005 Metric], Thick Film, General Purpose")
      (fields
        (field (name "MANUFACTURER") "Panasonic")
        (field (name "CASE CODE (IMPERIAL)") "0402")
        (field (name "TOLERANCE") "5%")
        (field (name "RESISTANCE") "0R")
      )
      (libsource (lib "Electronic Devices_LIB") (part "RES_0R_5%_100mW_0402"))
    )
    (comp (ref "R43")
      (value "ERJ-2GE0R00X")
      (footprint "RES_0402_RESC1005X04N")
      (description "SMD Chip Resistor, Jumper, 0 ohm, 100 mW, 0402 [1005 Metric], Thick Film, General Purpose")
      (fields
        (field (name "MANUFACTURER") "Panasonic")
        (field (name "CASE CODE (IMPERIAL)") "0402")
        (field (name "TOLERANCE") "5%")
        (field (name "RESISTANCE") "0R")
      )
      (libsource (lib "Electronic Devices_LIB") (part "RES_0R_5%_100mW_0402"))
    )
    (comp (ref "R44")
      (value "ERJ-2GE0R00X")
      (footprint "RES_0402_RESC1005X04N")
      (description "SMD Chip Resistor, Jumper, 0 ohm, 100 mW, 0402 [1005 Metric], Thick Film, General Purpose")
      (fields
        (field (name "MANUFACTURER") "Panasonic")
        (field (name "CASE CODE (IMPERIAL)") "0402")
        (field (name "TOLERANCE") "5%")
        (field (name "RESISTANCE") "0R")
      )
      (libsource (lib "Electronic Devices_LIB") (part "RES_0R_5%_100mW_0402"))
    )
    (comp (ref "R45")
      (value "ERJ-2GE0R00X")
      (footprint "RES_0402_RESC1005X04N")
      (description "SMD Chip Resistor, Jumper, 0 ohm, 100 mW, 0402 [1005 Metric], Thick Film, General Purpose")
      (fields
        (field (name "MANUFACTURER") "Panasonic")
        (field (name "CASE CODE (IMPERIAL)") "0402")
        (field (name "TOLERANCE") "5%")
        (field (name "RESISTANCE") "0R")
      )
      (libsource (lib "Electronic Devices_LIB") (part "RES_0R_5%_100mW_0402"))
    )
    (comp (ref "R46")
      (value "ERJ-2GE0R00X")
      (footprint "RES_0402_RESC1005X04N")
      (description "SMD Chip Resistor, Jumper, 0 ohm, 100 mW, 0402 [1005 Metric], Thick Film, General Purpose")
      (fields
        (field (name "MANUFACTURER") "Panasonic")
        (field (name "CASE CODE (IMPERIAL)") "0402")
        (field (name "TOLERANCE") "5%")
        (field (name "RESISTANCE") "0R")
      )
      (libsource (lib "Electronic Devices_LIB") (part "RES_0R_5%_100mW_0402"))
    )
    (comp (ref "R47")
      (value "ERJ-2GE0R00X")
      (footprint "RES_0402_RESC1005X04N")
      (description "SMD Chip Resistor, Jumper, 0 ohm, 100 mW, 0402 [1005 Metric], Thick Film, General Purpose")
      (fields
        (field (name "MANUFACTURER") "Panasonic")
        (field (name "CASE CODE (IMPERIAL)") "0402")
        (field (name "TOLERANCE") "5%")
        (field (name "RESISTANCE") "0R")
      )
      (libsource (lib "Electronic Devices_LIB") (part "RES_0R_5%_100mW_0402"))
    )
    (comp (ref "R48")
      (value "ERJ-2GE0R00X")
      (footprint "RES_0402_RESC1005X04N")
      (description "SMD Chip Resistor, Jumper, 0 ohm, 100 mW, 0402 [1005 Metric], Thick Film, General Purpose")
      (fields
        (field (name "MANUFACTURER") "Panasonic")
        (field (name "CASE CODE (IMPERIAL)") "0402")
        (field (name "TOLERANCE") "5%")
        (field (name "RESISTANCE") "0R")
      )
      (libsource (lib "Electronic Devices_LIB") (part "RES_0R_5%_100mW_0402"))
    )
    (comp (ref "R49")
      (value "ERJ-2GE0R00X")
      (footprint "RES_0402_RESC1005X04N")
      (description "SMD Chip Resistor, Jumper, 0 ohm, 100 mW, 0402 [1005 Metric], Thick Film, General Purpose")
      (fields
        (field (name "MANUFACTURER") "Panasonic")
        (field (name "CASE CODE (IMPERIAL)") "0402")
        (field (name "TOLERANCE") "5%")
        (field (name "RESISTANCE") "0R")
      )
      (libsource (lib "Electronic Devices_LIB") (part "RES_0R_5%_100mW_0402"))
    )
    (comp (ref "R50")
      (value "ERJ-2GE0R00X")
      (footprint "RES_0402_RESC1005X04N")
      (description "SMD Chip Resistor, Jumper, 0 ohm, 100 mW, 0402 [1005 Metric], Thick Film, General Purpose")
      (fields
        (field (name "MANUFACTURER") "Panasonic")
        (field (name "CASE CODE (IMPERIAL)") "0402")
        (field (name "TOLERANCE") "5%")
        (field (name "RESISTANCE") "0R")
      )
      (libsource (lib "Electronic Devices_LIB") (part "RES_0R_5%_100mW_0402"))
    )
    (comp (ref "R51")
      (value "ERJ-2GE0R00X")
      (footprint "RES_0402_RESC1005X04N")
      (description "SMD Chip Resistor, Jumper, 0 ohm, 100 mW, 0402 [1005 Metric], Thick Film, General Purpose")
      (fields
        (field (name "MANUFACTURER") "Panasonic")
        (field (name "CASE CODE (IMPERIAL)") "0402")
        (field (name "TOLERANCE") "5%")
        (field (name "RESISTANCE") "0R")
      )
      (libsource (lib "Electronic Devices_LIB") (part "RES_0R_5%_100mW_0402"))
    )
    (comp (ref "R52")
      (value "ERJ-2GE0R00X")
      (footprint "RES_0402_RESC1005X04N")
      (description "SMD Chip Resistor, Jumper, 0 ohm, 100 mW, 0402 [1005 Metric], Thick Film, General Purpose")
      (fields
        (field (name "MANUFACTURER") "Panasonic")
        (field (name "CASE CODE (IMPERIAL)") "0402")
        (field (name "TOLERANCE") "5%")
        (field (name "RESISTANCE") "0R")
      )
      (libsource (lib "Electronic Devices_LIB") (part "RES_0R_5%_100mW_0402"))
    )
    (comp (ref "U7")
      (value "MIMX8MD6DVAJZAB")
      (footprint "IC_MPU_BGA621C65P25X25_1700X1700X218")
      (fields (field (name "MANUFACTURER") "NXP Semiconductors"))
      (libsource (lib "Electronic Devices_LIB") (part "IC_MPU_ARM_1.5GHZ_MIMX8MD6DVAJZAB"))
    )
  )
  (nets
    (net (code "1") (name "GND") (class "Default")
      (node (ref "C100") (pin "1") (pinfunction "1_1") (pintype "passive"))
      (node (ref "C101") (pin "1") (pinfunction "1_1") (pintype "passive"))
      (node (ref "C102") (pin "1") (pinfunction "1_1") (pintype "passive"))
      (node (ref "C103") (pin "1") (pinfunction "1_1") (pintype "passive"))
      (node (ref "C104") (pin "1") (pinfunction "1_1") (pintype "passive"))
      (node (ref "C105") (pin "1") (pinfunction "1_1") (pintype "passive"))
      (node (ref "C106") (pin "1") (pinfunction "1_1") (pintype "passive"))
      (node (ref "C107") (pin "1") (pinfunction "1_1") (pintype "passive"))
      (node (ref "C108") (pin "1") (pinfunction "1_1") (pintype "passive"))
      (node (ref "C109") (pin "1") (pinfunction "1_1") (pintype "passive"))
      (node (ref "C110") (pin "1") (pinfunction "1_1") (pintype "passive"))
      (node (ref "C111") (pin "2") (pinfunction "2_2") (pintype "passive"))
      (node (ref "C112") (pin "1") (pinfunction "1_1") (pintype "passive"))
      (node (ref "C113") (pin "1") (pinfunction "1_1") (pintype "passive"))
      (node (ref "C114") (pin "1") (pinfunction "1_1") (pintype "passive"))
      (node (ref "C115") (pin "1") (pinfunction "1_1") (pintype "passive"))
      (node (ref "C116") (pin "1") (pinfunction "1_1") (pintype "passive"))
      (node (ref "C117") (pin "1") (pinfunction "1_1") (pintype "passive"))
      (node (ref "C118") (pin "1") (pinfunction "1_1") (pintype "passive"))
      (node (ref "C119") (pin "1") (pinfunction "1_1") (pintype "passive"))
      (node (ref "C120") (pin "1") (pinfunction "1_1") (pintype "passive"))
      (node (ref "C121") (pin "1") (pinfunction "1_1") (pintype "passive"))
      (node (ref "C122") (pin "1") (pinfunction "1_1") (pintype "passive"))
      (node (ref "C123") (pin "1") (pinfunction "1_1") (pintype "passive"))
      (node (ref "C124") (pin "1") (pinfunction "1_1") (pintype "passive"))
      (node (ref "C125") (pin "1") (pinfunction "1_1") (pintype "passive"))
      (node (ref "C126") (pin "1") (pinfunction "1_1") (pintype "passive"))
      (node (ref "C127") (pin "1") (pinfunction "1_1") (pintype "passive"))
      (node (ref "C128") (pin "1") (pinfunction "1_1") (pintype "passive"))
      (node (ref "C129") (pin "1") (pinfunction "1_1") (pintype "passive"))
      (node (ref "C130") (pin "1") (pinfunction "1_1") (pintype "passive"))
      (node (ref "C131") (pin "1") (pinfunction "1_1") (pintype "passive"))
      (node (ref "C132") (pin "1") (pinfunction "1_1") (pintype "passive"))
      (node (ref "C133") (pin "1") (pinfunction "1_1") (pintype "passive"))
      (node (ref "C134") (pin "1") (pinfunction "1_1") (pintype "passive"))
      (node (ref "C135") (pin "1") (pinfunction "1_1") (pintype "passive"))
      (node (ref "C136") (pin "1") (pinfunction "1_1") (pintype "passive"))
      (node (ref "C137") (pin "1") (pinfunction "1_1") (pintype "passive"))
      (node (ref "C138") (pin "1") (pinfunction "1_1") (pintype "passive"))
      (node (ref "C139") (pin "1") (pinfunction "1_1") (pintype "passive"))
      (node (ref "C140") (pin "1") (pinfunction "1_1") (pintype "passive"))
      (node (ref "C141") (pin "1") (pinfunction "1_1") (pintype "passive"))
      (node (ref "C142") (pin "1") (pinfunction "1_1") (pintype "passive"))
      (node (ref "C143") (pin "1") (pinfunction "1_1") (pintype "passive"))
      (node (ref "C144") (pin "1") (pinfunction "1_1") (pintype "passive"))
      (node (ref "C145") (pin "1") (pinfunction "1_1") (pintype "passive"))
      (node (ref "C146") (pin "1") (pinfunction "1_1") (pintype "passive"))
      (node (ref "C147") (pin "1") (pinfunction "1_1") (pintype "passive"))
      (node (ref "C148") (pin "1") (pinfunction "1_1") (pintype "passive"))
      (node (ref "C149") (pin "1") (pinfunction "1_1") (pintype "passive"))
      (node (ref "C150") (pin "1") (pinfunction "1_1") (pintype "passive"))
      (node (ref "C151") (pin "1") (pinfunction "1_1") (pintype "passive"))
      (node (ref "C152") (pin "1") (pinfunction "1_1") (pintype "passive"))
      (node (ref "C153") (pin "1") (pinfunction "1_1") (pintype "passive"))
      (node (ref "C154") (pin "1") (pinfunction "1_1") (pintype "passive"))
      (node (ref "C155") (pin "1") (pinfunction "1_1") (pintype "passive"))
      (node (ref "C156") (pin "1") (pinfunction "1_1") (pintype "passive"))
      (node (ref "C157") (pin "1") (pinfunction "1_1") (pintype "passive"))
      (node (ref "C158") (pin "1") (pinfunction "1_1") (pintype "passive"))
      (node (ref "C159") (pin "1") (pinfunction "1_1") (pintype "passive"))
      (node (ref "C160") (pin "1") (pinfunction "1_1") (pintype "passive"))
      (node (ref "C161") (pin "1") (pinfunction "1_1") (pintype "passive"))
      (node (ref "C162") (pin "1") (pinfunction "1_1") (pintype "passive"))
      (node (ref "C163") (pin "1") (pinfunction "1_1") (pintype "passive"))
      (node (ref "C164") (pin "1") (pinfunction "1_1") (pintype "passive"))
      (node (ref "C165") (pin "1") (pinfunction "1_1") (pintype "passive"))
      (node (ref "C166") (pin "1") (pinfunction "1_1") (pintype "passive"))
      (node (ref "C167") (pin "1") (pinfunction "1_1") (pintype "passive"))
      (node (ref "C168") (pin "1") (pinfunction "1_1") (pintype "passive"))
      (node (ref "C169") (pin "1") (pinfunction "1_1") (pintype "passive"))
      (node (ref "C170") (pin "1") (pinfunction "1_1") (pintype "passive"))
      (node (ref "C171") (pin "1") (pinfunction "1_1") (pintype "passive"))
      (node (ref "C172") (pin "1") (pinfunction "1_1") (pintype "passive"))
      (node (ref "C173") (pin "1") (pinfunction "1_1") (pintype "passive"))
      (node (ref "C174") (pin "1") (pinfunction "1_1") (pintype "passive"))
      (node (ref "C175") (pin "1") (pinfunction "1_1") (pintype "passive"))
      (node (ref "C176") (pin "1") (pinfunction "1_1") (pintype "passive"))
      (node (ref "C177") (pin "1") (pinfunction "1_1") (pintype "passive"))
      (node (ref "C178") (pin "1") (pinfunction "1_1") (pintype "passive"))
      (node (ref "C179") (pin "1") (pinfunction "1_1") (pintype "passive"))
      (node (ref "C180") (pin "1") (pinfunction "1_1") (pintype "passive"))
      (node (ref "C181") (pin "1") (pinfunction "1_1") (pintype "passive"))
      (node (ref "C182") (pin "1") (pinfunction "1_1") (pintype "passive"))
      (node (ref "C183") (pin "1") (pinfunction "1_1") (pintype "passive"))
      (node (ref "C184") (pin "1") (pinfunction "1_1") (pintype "passive"))
      (node (ref "C185") (pin "1") (pinfunction "1_1") (pintype "passive"))
      (node (ref "C186") (pin "1") (pinfunction "1_1") (pintype "passive"))
      (node (ref "C187") (pin "1") (pinfunction "1_1") (pintype "passive"))
      (node (ref "C188") (pin "1") (pinfunction "1_1") (pintype "passive"))
      (node (ref "C189") (pin "1") (pinfunction "1_1") (pintype "passive"))
      (node (ref "C190") (pin "1") (pinfunction "1_1") (pintype "passive"))
      (node (ref "C191") (pin "1") (pinfunction "1_1") (pintype "passive"))
      (node (ref "C192") (pin "1") (pinfunction "1_1") (pintype "passive"))
      (node (ref "C193") (pin "1") (pinfunction "1_1") (pintype "passive"))
      (node (ref "C194") (pin "1") (pinfunction "1_1") (pintype "passive"))
      (node (ref "C195") (pin "1") (pinfunction "1_1") (pintype "passive"))
      (node (ref "C196") (pin "1") (pinfunction "1_1") (pintype "passive"))
      (node (ref "C197") (pin "1") (pinfunction "1_1") (pintype "passive"))
      (node (ref "C198") (pin "1") (pinfunction "1_1") (pintype "passive"))
      (node (ref "C199") (pin "1") (pinfunction "1_1") (pintype "passive"))
      (node (ref "C200") (pin "1") (pinfunction "1_1") (pintype "passive"))
      (node (ref "C201") (pin "1") (pinfunction "1_1") (pintype "passive"))
      (node (ref "C202") (pin "1") (pinfunction "1_1") (pintype "passive"))
      (node (ref "C203") (pin "1") (pinfunction "1_1") (pintype "passive"))
      (node (ref "C204") (pin "1") (pinfunction "1_1") (pintype "passive"))
      (node (ref "C205") (pin "1") (pinfunction "1_1") (pintype "passive"))
      (node (ref "C206") (pin "1") (pinfunction "1_1") (pintype "passive"))
      (node (ref "C207") (pin "1") (pinfunction "1_1") (pintype "passive"))
      (node (ref "C208") (pin "1") (pinfunction "1_1") (pintype "passive"))
      (node (ref "C209") (pin "1") (pinfunction "1_1") (pintype "passive"))
      (node (ref "C210") (pin "1") (pinfunction "1_1") (pintype "passive"))
      (node (ref "C211") (pin "1") (pinfunction "1_1") (pintype "passive"))
      (node (ref "C212") (pin "1") (pinfunction "1_1") (pintype "passive"))
      (node (ref "C84") (pin "1") (pinfunction "1_1") (pintype "passive"))
      (node (ref "C85") (pin "1") (pinfunction "1_1") (pintype "passive"))
      (node (ref "C86") (pin "1") (pinfunction "1_1") (pintype "passive"))
      (node (ref "C87") (pin "1") (pinfunction "1_1") (pintype "passive"))
      (node (ref "C88") (pin "1") (pinfunction "1_1") (pintype "passive"))
      (node (ref "C89") (pin "1") (pinfunction "1_1") (pintype "passive"))
      (node (ref "C90") (pin "1") (pinfunction "1_1") (pintype "passive"))
      (node (ref "C91") (pin "1") (pinfunction "1_1") (pintype "passive"))
      (node (ref "C92") (pin "1") (pinfunction "1_1") (pintype "passive"))
      (node (ref "C93") (pin "1") (pinfunction "1_1") (pintype "passive"))
      (node (ref "C94") (pin "1") (pinfunction "1_1") (pintype "passive"))
      (node (ref "C95") (pin "1") (pinfunction "1_1") (pintype "passive"))
      (node (ref "C96") (pin "1") (pinfunction "1_1") (pintype "passive"))
      (node (ref "C97") (pin "1") (pinfunction "1_1") (pintype "passive"))
      (node (ref "C98") (pin "1") (pinfunction "1_1") (pintype "passive"))
      (node (ref "C99") (pin "1") (pinfunction "1_1") (pintype "passive"))
      (node (ref "U7") (pin "A2") (pinfunction "VSS_1_A2") (pintype "passive"))
      (node (ref "U7") (pin "A24") (pinfunction "VSS_2_A24") (pintype "passive"))
      (node (ref "U7") (pin "AA16") (pinfunction "VSS_121_AA16") (pintype "passive"))
      (node (ref "U7") (pin "AA21") (pinfunction "VSS_122_AA21") (pintype "passive"))
      (node (ref "U7") (pin "AA5") (pinfunction "VSS_120_AA5") (pintype "passive"))
      (node (ref "U7") (pin "AB11") (pinfunction "VSS_125_AB11") (pintype "passive"))
      (node (ref "U7") (pin "AB18") (pinfunction "VSS_126_AB18") (pintype "passive"))
      (node (ref "U7") (pin "AB2") (pinfunction "VSS_123_AB2") (pintype "passive"))
      (node (ref "U7") (pin "AB24") (pinfunction "VSS_127_AB24") (pintype "passive"))
      (node (ref "U7") (pin "AB9") (pinfunction "VSS_124_AB9") (pintype "passive"))
      (node (ref "U7") (pin "AC19") (pinfunction "VSS_129_AC19") (pintype "passive"))
      (node (ref "U7") (pin "AC22") (pinfunction "VSS_130_AC22") (pintype "passive"))
      (node (ref "U7") (pin "AC4") (pinfunction "VSS_128_AC4") (pintype "passive"))
      (node (ref "U7") (pin "AD1") (pinfunction "VSS_131_AD1") (pintype "passive"))
      (node (ref "U7") (pin "AD11") (pinfunction "VSS_134_AD11") (pintype "passive"))
      (node (ref "U7") (pin "AD13") (pinfunction "VSS_135_AD13") (pintype "passive"))
      (node (ref "U7") (pin "AD16") (pinfunction "VSS_136_AD16") (pintype "passive"))
      (node (ref "U7") (pin "AD25") (pinfunction "VSS_137_AD25") (pintype "passive"))
      (node (ref "U7") (pin "AD7") (pinfunction "VSS_132_AD7") (pintype "passive"))
      (node (ref "U7") (pin "AD9") (pinfunction "VSS_133_AD9") (pintype "passive"))
      (node (ref "U7") (pin "AE2") (pinfunction "VSS_138_AE2") (pintype "passive"))
      (node (ref "U7") (pin "AE21") (pinfunction "VSS_140_AE21") (pintype "passive"))
      (node (ref "U7") (pin "AE24") (pinfunction "VSS_141_AE24") (pintype "passive"))
      (node (ref "U7") (pin "AE5") (pinfunction "VSS_139_AE5") (pintype "passive"))
      (node (ref "U7") (pin "B1") (pinfunction "VSS_3_B1") (pintype "passive"))
      (node (ref "U7") (pin "B25") (pinfunction "VSS_4_B25") (pintype "passive"))
      (node (ref "U7") (pin "C10") (pinfunction "VSS_6_C10") (pintype "passive"))
      (node (ref "U7") (pin "C13") (pinfunction "VSS_7_C13") (pintype "passive"))
      (node (ref "U7") (pin "C15") (pinfunction "VSS_8_C15") (pintype "passive"))
      (node (ref "U7") (pin "C24") (pinfunction "VSS_9_C24") (pintype "passive"))
      (node (ref "U7") (pin "C8") (pinfunction "VSS_5_C8") (pintype "passive"))
      (node (ref "U7") (pin "D10") (pinfunction "VSS_10_D10") (pintype "passive"))
      (node (ref "U7") (pin "D13") (pinfunction "VSS_11_D13") (pintype "passive"))
      (node (ref "U7") (pin "D15") (pinfunction "VSS_12_D15") (pintype "passive"))
      (node (ref "U7") (pin "D23") (pinfunction "VSS_13_D23") (pintype "passive"))
      (node (ref "U7") (pin "E10") (pinfunction "VSS_15_E10") (pintype "passive"))
      (node (ref "U7") (pin "E13") (pinfunction "VSS_16_E13") (pintype "passive"))
      (node (ref "U7") (pin "E14") (pinfunction "VSS_17_E14") (pintype "passive"))
      (node (ref "U7") (pin "E16") (pinfunction "VSS_18_E16") (pintype "passive"))
      (node (ref "U7") (pin "E19") (pinfunction "VSS_19_E19") (pintype "passive"))
      (node (ref "U7") (pin "E20") (pinfunction "VSS_20_E20") (pintype "passive"))
      (node (ref "U7") (pin "E21") (pinfunction "VSS_21_E21") (pintype "passive"))
      (node (ref "U7") (pin "E22") (pinfunction "VSS_22_E22") (pintype "passive"))
      (node (ref "U7") (pin "E23") (pinfunction "VSS_23_E23") (pintype "passive"))
      (node (ref "U7") (pin "E4") (pinfunction "VSS_14_E4") (pintype "passive"))
      (node (ref "U7") (pin "F10") (pinfunction "VSS_24_F10") (pintype "passive"))
      (node (ref "U7") (pin "F13") (pinfunction "VSS_25_F13") (pintype "passive"))
      (node (ref "U7") (pin "F14") (pinfunction "VSS_26_F14") (pintype "passive"))
      (node (ref "U7") (pin "F16") (pinfunction "VSS_27_F16") (pintype "passive"))
      (node (ref "U7") (pin "F20") (pinfunction "VSS_28_F20") (pintype "passive"))
      (node (ref "U7") (pin "G10") (pinfunction "VSS_30_G10") (pintype "passive"))
      (node (ref "U7") (pin "G13") (pinfunction "VSS_31_G13") (pintype "passive"))
      (node (ref "U7") (pin "G17") (pinfunction "VSS_32_G17") (pintype "passive"))
      (node (ref "U7") (pin "G18") (pinfunction "VSS_33_G18") (pintype "passive"))
      (node (ref "U7") (pin "G24") (pinfunction "VSS_34_G24") (pintype "passive"))
      (node (ref "U7") (pin "G9") (pinfunction "VSS_29_G9") (pintype "passive"))
      (node (ref "U7") (pin "H10") (pinfunction "VSS_37_H10") (pintype "passive"))
      (node (ref "U7") (pin "H11") (pinfunction "VSS_38_H11") (pintype "passive"))
      (node (ref "U7") (pin "H12") (pinfunction "VSS_39_H12") (pintype "passive"))
      (node (ref "U7") (pin "H13") (pinfunction "VSS_40_H13") (pintype "passive"))
      (node (ref "U7") (pin "H17") (pinfunction "VSS_41_H17") (pintype "passive"))
      (node (ref "U7") (pin "H18") (pinfunction "VSS_42_H18") (pintype "passive"))
      (node (ref "U7") (pin "H8") (pinfunction "VSS_35_H8") (pintype "passive"))
      (node (ref "U7") (pin "H9") (pinfunction "VSS_36_H9") (pintype "passive"))
      (node (ref "U7") (pin "J11") (pinfunction "VSS_45_J11") (pintype "passive"))
      (node (ref "U7") (pin "J12") (pinfunction "VSS_46_J12") (pintype "passive"))
      (node (ref "U7") (pin "J13") (pinfunction "VSS_47_J13") (pintype "passive"))
      (node (ref "U7") (pin "J14") (pinfunction "VSS_48_J14") (pintype "passive"))
      (node (ref "U7") (pin "J17") (pinfunction "VSS_49_J17") (pintype "passive"))
      (node (ref "U7") (pin "J18") (pinfunction "VSS_50_J18") (pintype "passive"))
      (node (ref "U7") (pin "J19") (pinfunction "VSS_51_J19") (pintype "passive"))
      (node (ref "U7") (pin "J3") (pinfunction "VSS_43_J3") (pintype "passive"))
      (node (ref "U7") (pin "J8") (pinfunction "VSS_44_J8") (pintype "passive"))
      (node (ref "U7") (pin "K11") (pinfunction "VSS_53_K11") (pintype "passive"))
      (node (ref "U7") (pin "K13") (pinfunction "VSSA_FPLL_ARM_K13") (pintype "passive"))
      (node (ref "U7") (pin "K17") (pinfunction "VSS_54_K17") (pintype "passive"))
      (node (ref "U7") (pin "K18") (pinfunction "VSS_55_K18") (pintype "passive"))
      (node (ref "U7") (pin "K23") (pinfunction "VSS_56_K23") (pintype "passive"))
      (node (ref "U7") (pin "K8") (pinfunction "VSS_52_K8") (pintype "passive"))
      (node (ref "U7") (pin "L11") (pinfunction "VSS_58_L11") (pintype "passive"))
      (node (ref "U7") (pin "L14") (pinfunction "VSS_59_L14") (pintype "passive"))
      (node (ref "U7") (pin "L17") (pinfunction "VSS_60_L17") (pintype "passive"))
      (node (ref "U7") (pin "L8") (pinfunction "VSS_57_L8") (pintype "passive"))
      (node (ref "U7") (pin "M11") (pinfunction "VSS_62_M11") (pintype "passive"))
      (node (ref "U7") (pin "M14") (pinfunction "VSS_63_M14") (pintype "passive"))
      (node (ref "U7") (pin "M17") (pinfunction "VSS_64_M17") (pintype "passive"))
      (node (ref "U7") (pin "M8") (pinfunction "VSS_61_M8") (pintype "passive"))
      (node (ref "U7") (pin "N12") (pinfunction "VSSA_SPLL_VIDEO2_N12") (pintype "passive"))
      (node (ref "U7") (pin "N14") (pinfunction "VSS_66_N14") (pintype "passive"))
      (node (ref "U7") (pin "N15") (pinfunction "VSS_67_N15") (pintype "passive"))
      (node (ref "U7") (pin "N16") (pinfunction "VSS_68_N16") (pintype "passive"))
      (node (ref "U7") (pin "N17") (pinfunction "VSS_69_N17") (pintype "passive"))
      (node (ref "U7") (pin "N18") (pinfunction "VSS_70_N18") (pintype "passive"))
      (node (ref "U7") (pin "N3") (pinfunction "VSS_65_N3") (pintype "passive"))
      (node (ref "U7") (pin "P11") (pinfunction "VSS_73_P11") (pintype "passive"))
      (node (ref "U7") (pin "P14") (pinfunction "VSS_74_P14") (pintype "passive"))
      (node (ref "U7") (pin "P17") (pinfunction "VSS_75_P17") (pintype "passive"))
      (node (ref "U7") (pin "P18") (pinfunction "VSS_76_P18") (pintype "passive"))
      (node (ref "U7") (pin "P23") (pinfunction "VSS_77_P23") (pintype "passive"))
      (node (ref "U7") (pin "P6") (pinfunction "VSS_71_P6") (pintype "passive"))
      (node (ref "U7") (pin "P8") (pinfunction "VSS_72_P8") (pintype "passive"))
      (node (ref "U7") (pin "R7") (pinfunction "VSS_78_R7") (pintype "passive"))
      (node (ref "U7") (pin "T10") (pinfunction "VSS_82_T10") (pintype "passive"))
      (node (ref "U7") (pin "T11") (pinfunction "VSS_83_T11") (pintype "passive"))
      (node (ref "U7") (pin "T12") (pinfunction "VSS_84_T12") (pintype "passive"))
      (node (ref "U7") (pin "T13") (pinfunction "VSS_85_T13") (pintype "passive"))
      (node (ref "U7") (pin "T14") (pinfunction "VSSA_SPLL_DRAM_T14") (pintype "passive"))
      (node (ref "U7") (pin "T3") (pinfunction "VSS_79_T3") (pintype "passive"))
      (node (ref "U7") (pin "T4") (pinfunction "VSS_80_T4") (pintype "passive"))
      (node (ref "U7") (pin "T9") (pinfunction "VSS_81_T9") (pintype "passive"))
      (node (ref "U7") (pin "U15") (pinfunction "VSS_88_U15") (pintype "passive"))
      (node (ref "U7") (pin "U16") (pinfunction "VSSA_FPLL_U16") (pintype "passive"))
      (node (ref "U7") (pin "U18") (pinfunction "VSS_89_U18") (pintype "passive"))
      (node (ref "U7") (pin "U8") (pinfunction "VSS_86_U8") (pintype "passive"))
      (node (ref "U7") (pin "U9") (pinfunction "VSS_87_U9") (pintype "passive"))
      (node (ref "U7") (pin "V16") (pinfunction "VSS_92_V16") (pintype "passive"))
      (node (ref "U7") (pin "V17") (pinfunction "VSSA_SPLL_V17") (pintype "passive"))
      (node (ref "U7") (pin "V23") (pinfunction "VSSA_XTAL_25M_V23") (pintype "passive"))
      (node (ref "U7") (pin "V4") (pinfunction "VSS_90_V4") (pintype "passive"))
      (node (ref "U7") (pin "V8") (pinfunction "VSS_91_V8") (pintype "passive"))
      (node (ref "U7") (pin "W1") (pinfunction "VSS_93_W1") (pintype "passive"))
      (node (ref "U7") (pin "W10") (pinfunction "VSS_97_W10") (pintype "passive"))
      (node (ref "U7") (pin "W11") (pinfunction "VSS_98_W11") (pintype "passive"))
      (node (ref "U7") (pin "W12") (pinfunction "VSS_99_W12") (pintype "passive"))
      (node (ref "U7") (pin "W13") (pinfunction "VSS_100_W13") (pintype "passive"))
      (node (ref "U7") (pin "W14") (pinfunction "VSS_101_W14") (pintype "passive"))
      (node (ref "U7") (pin "W15") (pinfunction "VSS_102_W15") (pintype "passive"))
      (node (ref "U7") (pin "W16") (pinfunction "VSS_103_W16") (pintype "passive"))
      (node (ref "U7") (pin "W22") (pinfunction "VSSA_XTAL_27M_W22") (pintype "passive"))
      (node (ref "U7") (pin "W25") (pinfunction "VSS_104_W25") (pintype "passive"))
      (node (ref "U7") (pin "W7") (pinfunction "VSS_94_W7") (pintype "passive"))
      (node (ref "U7") (pin "W8") (pinfunction "VSS_95_W8") (pintype "passive"))
      (node (ref "U7") (pin "W9") (pinfunction "VSS_96_W9") (pintype "passive"))
      (node (ref "U7") (pin "Y11") (pinfunction "VSS_111_Y11") (pintype "passive"))
      (node (ref "U7") (pin "Y13") (pinfunction "VSS_112_Y13") (pintype "passive"))
      (node (ref "U7") (pin "Y15") (pinfunction "VSS_113_Y15") (pintype "passive"))
      (node (ref "U7") (pin "Y17") (pinfunction "VSS_114_Y17") (pintype "passive"))
      (node (ref "U7") (pin "Y19") (pinfunction "VSS_115_Y19") (pintype "passive"))
      (node (ref "U7") (pin "Y2") (pinfunction "VSS_105_Y2") (pintype "passive"))
      (node (ref "U7") (pin "Y21") (pinfunction "VSS_116_Y21") (pintype "passive"))
      (node (ref "U7") (pin "Y22") (pinfunction "VSS_117_Y22") (pintype "passive"))
      (node (ref "U7") (pin "Y23") (pinfunction "VSS_118_Y23") (pintype "passive"))
      (node (ref "U7") (pin "Y24") (pinfunction "VSS_119_Y24") (pintype "passive"))
      (node (ref "U7") (pin "Y3") (pinfunction "VSS_106_Y3") (pintype "passive"))
      (node (ref "U7") (pin "Y4") (pinfunction "VSS_107_Y4") (pintype "passive"))
      (node (ref "U7") (pin "Y5") (pinfunction "VSS_108_Y5") (pintype "passive"))
      (node (ref "U7") (pin "Y7") (pinfunction "VSS_109_Y7") (pintype "passive"))
      (node (ref "U7") (pin "Y9") (pinfunction "VSS_110_Y9") (pintype "passive"))
    )
    (net (code "2") (name "NVCC_3V3") (class "Default")
      (node (ref "C84") (pin "2") (pinfunction "2_2") (pintype "passive"))
      (node (ref "C85") (pin "2") (pinfunction "2_2") (pintype "passive"))
      (node (ref "C86") (pin "2") (pinfunction "2_2") (pintype "passive"))
      (node (ref "C87") (pin "2") (pinfunction "2_2") (pintype "passive"))
      (node (ref "C88") (pin "2") (pinfunction "2_2") (pintype "passive"))
      (node (ref "C89") (pin "2") (pinfunction "2_2") (pintype "passive"))
      (node (ref "C90") (pin "2") (pinfunction "2_2") (pintype "passive"))
      (node (ref "C91") (pin "2") (pinfunction "2_2") (pintype "passive"))
      (node (ref "C92") (pin "2") (pinfunction "2_2") (pintype "passive"))
      (node (ref "R41") (pin "2") (pinfunction "2_2") (pintype "passive"))
      (node (ref "U7") (pin "D8") (pinfunction "NVCC_UART_D8") (pintype "passive"))
      (node (ref "U7") (pin "E3") (pinfunction "NVCC_SAI3_E3") (pintype "passive"))
      (node (ref "U7") (pin "F5") (pinfunction "NVCC_ECSPI_F5") (pintype "passive"))
      (node (ref "U7") (pin "H7") (pinfunction "NVCC_I2C_H7") (pintype "passive"))
      (node (ref "U7") (pin "J7") (pinfunction "NVCC_SAI2_J7") (pintype "passive"))
      (node (ref "U7") (pin "K3") (pinfunction "NVCC_SAI1_1_K3") (pintype "passive"))
      (node (ref "U7") (pin "L18") (pinfunction "NVCC_NAND_1_L18") (pintype "passive"))
      (node (ref "U7") (pin "L3") (pinfunction "NVCC_SAI1_2_L3") (pintype "passive"))
      (node (ref "U7") (pin "M18") (pinfunction "NVCC_NAND_2_M18") (pintype "passive"))
      (node (ref "U7") (pin "M3") (pinfunction "NVCC_SAI5_M3") (pintype "passive"))
      (node (ref "U7") (pin "R5") (pinfunction "NVCC_GPIO1_1_R5") (pintype "passive"))
      (node (ref "U7") (pin "R6") (pinfunction "NVCC_GPIO1_2_R6") (pintype "passive"))
      (node (ref "U7") (pin "W4") (pinfunction "NVCC_JTAG_W4") (pintype "passive"))
    )
    (net (code "3") (name "NVCC_DRAM_1V1") (class "Default")
      (node (ref "C192") (pin "2") (pinfunction "2_2") (pintype "passive"))
      (node (ref "C193") (pin "2") (pinfunction "2_2") (pintype "passive"))
      (node (ref "C194") (pin "2") (pinfunction "2_2") (pintype "passive"))
      (node (ref "C195") (pin "2") (pinfunction "2_2") (pintype "passive"))
      (node (ref "C196") (pin "2") (pinfunction "2_2") (pintype "passive"))
      (node (ref "C197") (pin "2") (pinfunction "2_2") (pintype "passive"))
      (node (ref "C198") (pin "2") (pinfunction "2_2") (pintype "passive"))
      (node (ref "C199") (pin "2") (pinfunction "2_2") (pintype "passive"))
      (node (ref "C200") (pin "2") (pinfunction "2_2") (pintype "passive"))
      (node (ref "C201") (pin "2") (pinfunction "2_2") (pintype "passive"))
      (node (ref "C202") (pin "2") (pinfunction "2_2") (pintype "passive"))
      (node (ref "C203") (pin "2") (pinfunction "2_2") (pintype "passive"))
      (node (ref "C204") (pin "2") (pinfunction "2_2") (pintype "passive"))
      (node (ref "C205") (pin "2") (pinfunction "2_2") (pintype "passive"))
      (node (ref "C206") (pin "2") (pinfunction "2_2") (pintype "passive"))
      (node (ref "C207") (pin "2") (pinfunction "2_2") (pintype "passive"))
      (node (ref "C208") (pin "2") (pinfunction "2_2") (pintype "passive"))
      (node (ref "C209") (pin "2") (pinfunction "2_2") (pintype "passive"))
      (node (ref "C210") (pin "2") (pinfunction "2_2") (pintype "passive"))
      (node (ref "C211") (pin "2") (pinfunction "2_2") (pintype "passive"))
      (node (ref "C212") (pin "2") (pinfunction "2_2") (pintype "passive"))
      (node (ref "U7") (pin "AA10") (pinfunction "NVCC_DRAM_3_AA10") (pintype "passive"))
      (node (ref "U7") (pin "AA15") (pinfunction "NVCC_DRAM_4_AA15") (pintype "passive"))
      (node (ref "U7") (pin "AB17") (pinfunction "NVCC_DRAM_7_AB17") (pintype "passive"))
      (node (ref "U7") (pin "AB23") (pinfunction "NVCC_DRAM_8_AB23") (pintype "passive"))
      (node (ref "U7") (pin "AB3") (pinfunction "NVCC_DRAM_5_AB3") (pintype "passive"))
      (node (ref "U7") (pin "AB8") (pinfunction "NVCC_DRAM_6_AB8") (pintype "passive"))
      (node (ref "U7") (pin "AC14") (pinfunction "NVCC_DRAM_12_AC14") (pintype "passive"))
      (node (ref "U7") (pin "AC17") (pinfunction "NVCC_DRAM_13_AC17") (pintype "passive"))
      (node (ref "U7") (pin "AC20") (pinfunction "NVCC_DRAM_14_AC20") (pintype "passive"))
      (node (ref "U7") (pin "AC23") (pinfunction "NVCC_DRAM_15_AC23") (pintype "passive"))
      (node (ref "U7") (pin "AC3") (pinfunction "NVCC_DRAM_9_AC3") (pintype "passive"))
      (node (ref "U7") (pin "AC6") (pinfunction "NVCC_DRAM_10_AC6") (pintype "passive"))
      (node (ref "U7") (pin "AC8") (pinfunction "NVCC_DRAM_11_AC8") (pintype "passive"))
      (node (ref "U7") (pin "AD18") (pinfunction "NVCC_DRAM_17_AD18") (pintype "passive"))
      (node (ref "U7") (pin "AD21") (pinfunction "NVCC_DRAM_18_AD21") (pintype "passive"))
      (node (ref "U7") (pin "AD5") (pinfunction "NVCC_DRAM_16_AD5") (pintype "passive"))
      (node (ref "U7") (pin "Y12") (pinfunction "NVCC_DRAM_1_Y12") (pintype "passive"))
      (node (ref "U7") (pin "Y14") (pinfunction "NVCC_DRAM_2_Y14") (pintype "passive"))
    )
    (net (code "4") (name "NVCC_ECSPI_3V3") (class "Default")
      (node (ref "R51") (pin "2") (pinfunction "2_2") (pintype "passive"))
    )
    (net (code "5") (name "NVCC_ENET_2V5") (class "Default")
      (node (ref "C104") (pin "2") (pinfunction "2_2") (pintype "passive"))
      (node (ref "U7") (pin "T18") (pinfunction "NVCC_ENET_T18") (pintype "passive"))
    )
    (net (code "6") (name "NVCC_GPIO_3V3") (class "Default")
      (node (ref "R43") (pin "2") (pinfunction "2_2") (pintype "passive"))
    )
    (net (code "7") (name "NVCC_I2C_3V3") (class "Default")
      (node (ref "R50") (pin "2") (pinfunction "2_2") (pintype "passive"))
    )
    (net (code "8") (name "NVCC_JTAG_3V3") (class "Default")
      (node (ref "R42") (pin "2") (pinfunction "2_2") (pintype "passive"))
    )
    (net (code "9") (name "NVCC_NAND_3V3") (class "Default")
      (node (ref "R45") (pin "2") (pinfunction "2_2") (pintype "passive"))
    )
    (net (code "10") (name "NVCC_SAI1_3V3") (class "Default")
      (node (ref "R46") (pin "2") (pinfunction "2_2") (pintype "passive"))
    )
    (net (code "11") (name "NVCC_SAI2_3V3") (class "Default")
      (node (ref "R47") (pin "2") (pinfunction "2_2") (pintype "passive"))
    )
    (net (code "12") (name "NVCC_SAI3_3V3") (class "Default")
      (node (ref "R48") (pin "2") (pinfunction "2_2") (pintype "passive"))
    )
    (net (code "13") (name "NVCC_SAI5_3V3") (class "Default")
      (node (ref "R49") (pin "2") (pinfunction "2_2") (pintype "passive"))
    )
    (net (code "14") (name "NVCC_SD1_1V8") (class "Default")
      (node (ref "C102") (pin "2") (pinfunction "2_2") (pintype "passive"))
      (node (ref "U7") (pin "L23") (pinfunction "NVCC_SD1_1_L23") (pintype "passive"))
      (node (ref "U7") (pin "M23") (pinfunction "NVCC_SD1_2_M23") (pintype "passive"))
    )
    (net (code "15") (name "NVCC_SD2") (class "Default")
      (node (ref "C103") (pin "2") (pinfunction "2_2") (pintype "passive"))
      (node (ref "R52") (pin "2") (pinfunction "2_2") (pintype "passive"))
      (node (ref "U7") (pin "N23") (pinfunction "NVCC_SD2_N23") (pintype "passive"))
    )
    (net (code "16") (name "NVCC_SNVS_3V3") (class "Default")
      (node (ref "C93") (pin "2") (pinfunction "2_2") (pintype "passive"))
      (node (ref "U7") (pin "W18") (pinfunction "NVCC_SNVS_W18") (pintype "passive"))
    )
    (net (code "17") (name "NVCC_UART_3V3") (class "Default")
      (node (ref "R44") (pin "2") (pinfunction "2_2") (pintype "passive"))
    )
    (net (code "18") (name "Net-(U7A-MIPI_VDD_1)") (class "Default")
      (node (ref "C173") (pin "2") (pinfunction "2_2") (pintype "passive"))
      (node (ref "C174") (pin "2") (pinfunction "2_2") (pintype "passive"))
      (node (ref "L10") (pin "1") (pinfunction "1_1") (pintype "passive"))
      (node (ref "U7") (pin "E15") (pinfunction "MIPI_VDD_1_E15") (pintype "passive"))
      (node (ref "U7") (pin "F15") (pinfunction "MIPI_VDD_2_F15") (pintype "passive"))
    )
    (net (code "19") (name "Net-(U7A-VDDA_0P9)") (class "Default")
      (node (ref "C111") (pin "1") (pinfunction "1_1") (pintype "passive"))
      (node (ref "L9") (pin "1") (pinfunction "1_1") (pintype "passive"))
      (node (ref "U7") (pin "V18") (pinfunction "VDDA_0P9_V18") (pintype "passive"))
    )
    (net (code "20") (name "VDDA_1V8") (class "Default")
      (node (ref "C185") (pin "2") (pinfunction "2_2") (pintype "passive"))
      (node (ref "C186") (pin "2") (pinfunction "2_2") (pintype "passive"))
      (node (ref "C187") (pin "2") (pinfunction "2_2") (pintype "passive"))
      (node (ref "C188") (pin "2") (pinfunction "2_2") (pintype "passive"))
      (node (ref "C189") (pin "2") (pinfunction "2_2") (pintype "passive"))
      (node (ref "C190") (pin "2") (pinfunction "2_2") (pintype "passive"))
      (node (ref "C191") (pin "2") (pinfunction "2_2") (pintype "passive"))
      (node (ref "U7") (pin "AA11") (pinfunction "VDDA_DRAM_AA11") (pintype "passive"))
      (node (ref "U7") (pin "K14") (pinfunction "VDDA_1P8_FPLL-ARM_K14") (pintype "passive"))
      (node (ref "U7") (pin "N11") (pinfunction "VDDA_1P8_SPLL_VIDEO2_N11") (pintype "passive"))
      (node (ref "U7") (pin "R17") (pinfunction "EFUSE_VQPS_R17") (pintype "passive"))
      (node (ref "U7") (pin "T15") (pinfunction "VDDA_1P8_SPLL_DRAM_T15") (pintype "passive"))
      (node (ref "U7") (pin "T16") (pinfunction "VDDA_1P8_TSENSOR_T16") (pintype "passive"))
      (node (ref "U7") (pin "U17") (pinfunction "VDDA_1P8_FPLL_U17") (pintype "passive"))
      (node (ref "U7") (pin "U23") (pinfunction "VDDA_1P8_LVDS_U23") (pintype "passive"))
      (node (ref "U7") (pin "W17") (pinfunction "VDDA_1P8_SPLL_W17") (pintype "passive"))
      (node (ref "U7") (pin "W23") (pinfunction "VDDA_1P8_XTAL_27M_W23") (pintype "passive"))
      (node (ref "U7") (pin "W24") (pinfunction "VDDA_1P8_XTAL_25M_W24") (pintype "passive"))
    )
    (net (code "21") (name "VDD_3V3") (class "Default")
      (node (ref "R41") (pin "1") (pinfunction "1_1") (pintype "passive"))
      (node (ref "R42") (pin "1") (pinfunction "1_1") (pintype "passive"))
      (node (ref "R43") (pin "1") (pinfunction "1_1") (pintype "passive"))
      (node (ref "R44") (pin "1") (pinfunction "1_1") (pintype "passive"))
      (node (ref "R45") (pin "1") (pinfunction "1_1") (pintype "passive"))
      (node (ref "R46") (pin "1") (pinfunction "1_1") (pintype "passive"))
      (node (ref "R47") (pin "1") (pinfunction "1_1") (pintype "passive"))
      (node (ref "R48") (pin "1") (pinfunction "1_1") (pintype "passive"))
      (node (ref "R49") (pin "1") (pinfunction "1_1") (pintype "passive"))
      (node (ref "R50") (pin "1") (pinfunction "1_1") (pintype "passive"))
      (node (ref "R51") (pin "1") (pinfunction "1_1") (pintype "passive"))
      (node (ref "R52") (pin "1") (pinfunction "1_1") (pintype "passive"))
    )
    (net (code "22") (name "VDD_ARM_0V9") (class "Default")
      (node (ref "C115") (pin "2") (pinfunction "2_2") (pintype "passive"))
      (node (ref "C116") (pin "2") (pinfunction "2_2") (pintype "passive"))
      (node (ref "C117") (pin "2") (pinfunction "2_2") (pintype "passive"))
      (node (ref "C118") (pin "2") (pinfunction "2_2") (pintype "passive"))
      (node (ref "C119") (pin "2") (pinfunction "2_2") (pintype "passive"))
      (node (ref "C120") (pin "2") (pinfunction "2_2") (pintype "passive"))
      (node (ref "C121") (pin "2") (pinfunction "2_2") (pintype "passive"))
      (node (ref "C122") (pin "2") (pinfunction "2_2") (pintype "passive"))
      (node (ref "C126") (pin "2") (pinfunction "2_2") (pintype "passive"))
      (node (ref "C127") (pin "2") (pinfunction "2_2") (pintype "passive"))
      (node (ref "C128") (pin "2") (pinfunction "2_2") (pintype "passive"))
      (node (ref "C129") (pin "2") (pinfunction "2_2") (pintype "passive"))
      (node (ref "U7") (pin "G14") (pinfunction "VDD_ARM_1_G14") (pintype "passive"))
      (node (ref "U7") (pin "G15") (pinfunction "VDD_ARM_2_G15") (pintype "passive"))
      (node (ref "U7") (pin "G16") (pinfunction "VDD_ARM_3_G16") (pintype "passive"))
      (node (ref "U7") (pin "H14") (pinfunction "VDD_ARM_4_H14") (pintype "passive"))
      (node (ref "U7") (pin "H15") (pinfunction "VDD_ARM_5_H15") (pintype "passive"))
      (node (ref "U7") (pin "H16") (pinfunction "VDD_ARM_6_H16") (pintype "passive"))
      (node (ref "U7") (pin "J15") (pinfunction "VDD_ARM_7_J15") (pintype "passive"))
      (node (ref "U7") (pin "J16") (pinfunction "VDD_ARM_8_J16") (pintype "passive"))
      (node (ref "U7") (pin "K15") (pinfunction "VDD_ARM_9_K15") (pintype "passive"))
      (node (ref "U7") (pin "K16") (pinfunction "VDD_ARM_10_K16") (pintype "passive"))
      (node (ref "U7") (pin "L15") (pinfunction "VDD_ARM_11_L15") (pintype "passive"))
      (node (ref "U7") (pin "L16") (pinfunction "VDD_ARM_12_L16") (pintype "passive"))
      (node (ref "U7") (pin "M15") (pinfunction "VDD_ARM_13_M15") (pintype "passive"))
      (node (ref "U7") (pin "M16") (pinfunction "VDD_ARM_14_M16") (pintype "passive"))
    )
    (net (code "23") (name "VDD_DRAM_0V9") (class "Default")
      (node (ref "C159") (pin "2") (pinfunction "2_2") (pintype "passive"))
      (node (ref "C160") (pin "2") (pinfunction "2_2") (pintype "passive"))
      (node (ref "C161") (pin "2") (pinfunction "2_2") (pintype "passive"))
      (node (ref "C162") (pin "2") (pinfunction "2_2") (pintype "passive"))
      (node (ref "C163") (pin "2") (pinfunction "2_2") (pintype "passive"))
      (node (ref "C164") (pin "2") (pinfunction "2_2") (pintype "passive"))
      (node (ref "C165") (pin "2") (pinfunction "2_2") (pintype "passive"))
      (node (ref "C166") (pin "2") (pinfunction "2_2") (pintype "passive"))
      (node (ref "C167") (pin "2") (pinfunction "2_2") (pintype "passive"))
      (node (ref "C168") (pin "2") (pinfunction "2_2") (pintype "passive"))
      (node (ref "C175") (pin "2") (pinfunction "2_2") (pintype "passive"))
      (node (ref "C176") (pin "2") (pinfunction "2_2") (pintype "passive"))
      (node (ref "C177") (pin "2") (pinfunction "2_2") (pintype "passive"))
      (node (ref "C178") (pin "2") (pinfunction "2_2") (pintype "passive"))
      (node (ref "C179") (pin "2") (pinfunction "2_2") (pintype "passive"))
      (node (ref "C180") (pin "2") (pinfunction "2_2") (pintype "passive"))
      (node (ref "C181") (pin "2") (pinfunction "2_2") (pintype "passive"))
      (node (ref "C182") (pin "2") (pinfunction "2_2") (pintype "passive"))
      (node (ref "C183") (pin "2") (pinfunction "2_2") (pintype "passive"))
      (node (ref "C184") (pin "2") (pinfunction "2_2") (pintype "passive"))
      (node (ref "U7") (pin "U10") (pinfunction "VDD_DRAM_1_U10") (pintype "passive"))
      (node (ref "U7") (pin "U11") (pinfunction "VDD_DRAM_2_U11") (pintype "passive"))
      (node (ref "U7") (pin "U12") (pinfunction "VDD_DRAM_3_U12") (pintype "passive"))
      (node (ref "U7") (pin "U13") (pinfunction "VDD_DRAM_4_U13") (pintype "passive"))
      (node (ref "U7") (pin "U14") (pinfunction "VDD_DRAM_5_U14") (pintype "passive"))
      (node (ref "U7") (pin "V10") (pinfunction "VDD_DRAM_7_V10") (pintype "passive"))
      (node (ref "U7") (pin "V11") (pinfunction "VDD_DRAM_8_V11") (pintype "passive"))
      (node (ref "U7") (pin "V12") (pinfunction "VDD_DRAM_9_V12") (pintype "passive"))
      (node (ref "U7") (pin "V13") (pinfunction "VDD_DRAM_10_V13") (pintype "passive"))
      (node (ref "U7") (pin "V14") (pinfunction "VDD_DRAM_11_V14") (pintype "passive"))
      (node (ref "U7") (pin "V15") (pinfunction "VDD_DRAM_12_V15") (pintype "passive"))
      (node (ref "U7") (pin "V9") (pinfunction "VDD_DRAM_6_V9") (pintype "passive"))
      (node (ref "U7") (pin "Y10") (pinfunction "VDD_DRAM_15_Y10") (pintype "passive"))
      (node (ref "U7") (pin "Y16") (pinfunction "VDD_DRAM_16_Y16") (pintype "passive"))
      (node (ref "U7") (pin "Y18") (pinfunction "VDD_DRAM_17_Y18") (pintype "passive"))
      (node (ref "U7") (pin "Y20") (pinfunction "VDD_DRAM_18_Y20") (pintype "passive"))
      (node (ref "U7") (pin "Y6") (pinfunction "VDD_DRAM_13_Y6") (pintype "passive"))
      (node (ref "U7") (pin "Y8") (pinfunction "VDD_DRAM_14_Y8") (pintype "passive"))
    )
    (net (code "24") (name "VDD_GPU_0V9") (class "Default")
      (node (ref "C147") (pin "2") (pinfunction "2_2") (pintype "passive"))
      (node (ref "C148") (pin "2") (pinfunction "2_2") (pintype "passive"))
      (node (ref "C149") (pin "2") (pinfunction "2_2") (pintype "passive"))
      (node (ref "C150") (pin "2") (pinfunction "2_2") (pintype "passive"))
      (node (ref "C151") (pin "2") (pinfunction "2_2") (pintype "passive"))
      (node (ref "C152") (pin "2") (pinfunction "2_2") (pintype "passive"))
      (node (ref "C153") (pin "2") (pinfunction "2_2") (pintype "passive"))
      (node (ref "C154") (pin "2") (pinfunction "2_2") (pintype "passive"))
      (node (ref "C155") (pin "2") (pinfunction "2_2") (pintype "passive"))
      (node (ref "C156") (pin "2") (pinfunction "2_2") (pintype "passive"))
      (node (ref "U7") (pin "J10") (pinfunction "VDD_GPU_2_J10") (pintype "passive"))
      (node (ref "U7") (pin "J9") (pinfunction "VDD_GPU_1_J9") (pintype "passive"))
      (node (ref "U7") (pin "K10") (pinfunction "VDD_GPU_4_K10") (pintype "passive"))
      (node (ref "U7") (pin "K9") (pinfunction "VDD_GPU_3_K9") (pintype "passive"))
      (node (ref "U7") (pin "L10") (pinfunction "VDD_GPU_6_L10") (pintype "passive"))
      (node (ref "U7") (pin "L9") (pinfunction "VDD_GPU_5_L9") (pintype "passive"))
      (node (ref "U7") (pin "M10") (pinfunction "VDD_GPU_8_M10") (pintype "passive"))
      (node (ref "U7") (pin "M9") (pinfunction "VDD_GPU_7_M9") (pintype "passive"))
    )
    (net (code "25") (name "VDD_PHY_0V9") (class "Default")
      (node (ref "C123") (pin "2") (pinfunction "2_2") (pintype "passive"))
      (node (ref "C124") (pin "2") (pinfunction "2_2") (pintype "passive"))
      (node (ref "C125") (pin "2") (pinfunction "2_2") (pintype "passive"))
      (node (ref "C132") (pin "2") (pinfunction "2_2") (pintype "passive"))
      (node (ref "C133") (pin "2") (pinfunction "2_2") (pintype "passive"))
      (node (ref "C134") (pin "2") (pinfunction "2_2") (pintype "passive"))
      (node (ref "C142") (pin "2") (pinfunction "2_2") (pintype "passive"))
      (node (ref "C143") (pin "2") (pinfunction "2_2") (pintype "passive"))
      (node (ref "C144") (pin "2") (pinfunction "2_2") (pintype "passive"))
      (node (ref "C169") (pin "2") (pinfunction "2_2") (pintype "passive"))
      (node (ref "C170") (pin "2") (pinfunction "2_2") (pintype "passive"))
      (node (ref "C171") (pin "2") (pinfunction "2_2") (pintype "passive"))
      (node (ref "C172") (pin "2") (pinfunction "2_2") (pintype "passive"))
      (node (ref "L10") (pin "2") (pinfunction "2_2") (pintype "passive"))
      (node (ref "U7") (pin "C11") (pinfunction "USB2_VPTX_C11") (pintype "passive"))
      (node (ref "U7") (pin "C12") (pinfunction "USB1_VPTX_C12") (pintype "passive"))
      (node (ref "U7") (pin "D11") (pinfunction "USB2_VP_D11") (pintype "passive"))
      (node (ref "U7") (pin "D12") (pinfunction "USB1_VP_D12") (pintype "passive"))
      (node (ref "U7") (pin "E11") (pinfunction "USB2_DVDD_E11") (pintype "passive"))
      (node (ref "U7") (pin "E12") (pinfunction "USB1_DVDD_E12") (pintype "passive"))
      (node (ref "U7") (pin "E17") (pinfunction "MIPI_VDDA_1_E17") (pintype "passive"))
      (node (ref "U7") (pin "E18") (pinfunction "MIPI_VDDA_2_E18") (pintype "passive"))
      (node (ref "U7") (pin "F17") (pinfunction "MIPI_VDDA_3_F17") (pintype "passive"))
      (node (ref "U7") (pin "F18") (pinfunction "MIPI_VDDA_4_F18") (pintype "passive"))
      (node (ref "U7") (pin "F19") (pinfunction "MIPI_VDDPLL_F19") (pintype "passive"))
      (node (ref "U7") (pin "F22") (pinfunction "PCIE_VP_1_F22") (pintype "passive"))
      (node (ref "U7") (pin "F23") (pinfunction "PCIE_VPTX_1_F23") (pintype "passive"))
      (node (ref "U7") (pin "G22") (pinfunction "PCIE_VP_2_G22") (pintype "passive"))
      (node (ref "U7") (pin "G23") (pinfunction "PCIE_VPTX_2_G23") (pintype "passive"))
      (node (ref "U7") (pin "U3") (pinfunction "HDMI_AVDDCORE_1_U3") (pintype "passive"))
      (node (ref "U7") (pin "U4") (pinfunction "HDMI_AVDDCORE_2_U4") (pintype "passive"))
      (node (ref "U7") (pin "V3") (pinfunction "HDMI_AVDDCLK_V3") (pintype "passive"))
    )
    (net (code "26") (name "VDD_PHY_1V8") (class "Default")
      (node (ref "C145") (pin "2") (pinfunction "2_2") (pintype "passive"))
      (node (ref "C146") (pin "2") (pinfunction "2_2") (pintype "passive"))
      (node (ref "C157") (pin "2") (pinfunction "2_2") (pintype "passive"))
      (node (ref "C158") (pin "2") (pinfunction "2_2") (pintype "passive"))
      (node (ref "U7") (pin "C18") (pinfunction "MIPI_VDDHA_1_C18") (pintype "passive"))
      (node (ref "U7") (pin "D17") (pinfunction "MIPI_VDDHA_2_D17") (pintype "passive"))
      (node (ref "U7") (pin "D18") (pinfunction "MIPI_VDDHA_3_D18") (pintype "passive"))
      (node (ref "U7") (pin "P2") (pinfunction "HDMI_AVDDIO_P2") (pintype "passive"))
    )
    (net (code "27") (name "VDD_PHY_3V3") (class "Default")
      (node (ref "C112") (pin "2") (pinfunction "2_2") (pintype "passive"))
      (node (ref "C113") (pin "2") (pinfunction "2_2") (pintype "passive"))
      (node (ref "C114") (pin "2") (pinfunction "2_2") (pintype "passive"))
      (node (ref "C130") (pin "2") (pinfunction "2_2") (pintype "passive"))
      (node (ref "C131") (pin "2") (pinfunction "2_2") (pintype "passive"))
      (node (ref "U7") (pin "F11") (pinfunction "USB2_VPH_F11") (pintype "passive"))
      (node (ref "U7") (pin "F12") (pinfunction "USB1_VPH_F12") (pintype "passive"))
      (node (ref "U7") (pin "G11") (pinfunction "USB2_VDD33_G11") (pintype "passive"))
      (node (ref "U7") (pin "G12") (pinfunction "USB1_VDD33_G12") (pintype "passive"))
      (node (ref "U7") (pin "H23") (pinfunction "PCIE_VPH_1_H23") (pintype "passive"))
      (node (ref "U7") (pin "J23") (pinfunction "PCIE_VPH_2_J23") (pintype "passive"))
    )
    (net (code "28") (name "VDD_SNVS_0V9") (class "Default")
      (node (ref "C94") (pin "2") (pinfunction "2_2") (pintype "passive"))
      (node (ref "U7") (pin "R18") (pinfunction "VDD_SNVS_R18") (pintype "passive"))
    )
    (net (code "29") (name "VDD_SOC_0V9") (class "Default")
      (node (ref "C100") (pin "2") (pinfunction "2_2") (pintype "passive"))
      (node (ref "C101") (pin "2") (pinfunction "2_2") (pintype "passive"))
      (node (ref "C105") (pin "2") (pinfunction "2_2") (pintype "passive"))
      (node (ref "C106") (pin "2") (pinfunction "2_2") (pintype "passive"))
      (node (ref "C107") (pin "2") (pinfunction "2_2") (pintype "passive"))
      (node (ref "C108") (pin "2") (pinfunction "2_2") (pintype "passive"))
      (node (ref "C109") (pin "2") (pinfunction "2_2") (pintype "passive"))
      (node (ref "C110") (pin "2") (pinfunction "2_2") (pintype "passive"))
      (node (ref "C95") (pin "2") (pinfunction "2_2") (pintype "passive"))
      (node (ref "C96") (pin "2") (pinfunction "2_2") (pintype "passive"))
      (node (ref "C97") (pin "2") (pinfunction "2_2") (pintype "passive"))
      (node (ref "C98") (pin "2") (pinfunction "2_2") (pintype "passive"))
      (node (ref "C99") (pin "2") (pinfunction "2_2") (pintype "passive"))
      (node (ref "L9") (pin "2") (pinfunction "2_2") (pintype "passive"))
      (node (ref "U7") (pin "K12") (pinfunction "VDD_SOC_1_K12") (pintype "passive"))
      (node (ref "U7") (pin "L12") (pinfunction "VDD_SOC_2_L12") (pintype "passive"))
      (node (ref "U7") (pin "L13") (pinfunction "VDD_SOC_3_L13") (pintype "passive"))
      (node (ref "U7") (pin "M12") (pinfunction "VDD_SOC_4_M12") (pintype "passive"))
      (node (ref "U7") (pin "M13") (pinfunction "VDD_SOC_5_M13") (pintype "passive"))
      (node (ref "U7") (pin "N13") (pinfunction "VDD_SOC_6_N13") (pintype "passive"))
      (node (ref "U7") (pin "P12") (pinfunction "VDD_SOC_7_P12") (pintype "passive"))
      (node (ref "U7") (pin "P13") (pinfunction "VDD_SOC_8_P13") (pintype "passive"))
      (node (ref "U7") (pin "P15") (pinfunction "VDD_SOC_9_P15") (pintype "passive"))
      (node (ref "U7") (pin "P16") (pinfunction "VDD_SOC_10_P16") (pintype "passive"))
      (node (ref "U7") (pin "R10") (pinfunction "VDD_SOC_13_R10") (pintype "passive"))
      (node (ref "U7") (pin "R11") (pinfunction "VDD_SOC_14_R11") (pintype "passive"))
      (node (ref "U7") (pin "R12") (pinfunction "VDD_SOC_15_R12") (pintype "passive"))
      (node (ref "U7") (pin "R13") (pinfunction "VDD_SOC_16_R13") (pintype "passive"))
      (node (ref "U7") (pin "R14") (pinfunction "VDD_SOC_17_R14") (pintype "passive"))
      (node (ref "U7") (pin "R15") (pinfunction "VDD_SOC_18_R15") (pintype "passive"))
      (node (ref "U7") (pin "R16") (pinfunction "VDD_SOC_19_R16") (pintype "passive"))
      (node (ref "U7") (pin "R8") (pinfunction "VDD_SOC_11_R8") (pintype "passive"))
      (node (ref "U7") (pin "R9") (pinfunction "VDD_SOC_12_R9") (pintype "passive"))
      (node (ref "U7") (pin "T17") (pinfunction "VDD_SOC_21_T17") (pintype "passive"))
      (node (ref "U7") (pin "T8") (pinfunction "VDD_SOC_20_T8") (pintype "passive"))
    )
    (net (code "30") (name "VDD_VPU_0V9") (class "Default")
      (node (ref "C135") (pin "2") (pinfunction "2_2") (pintype "passive"))
      (node (ref "C136") (pin "2") (pinfunction "2_2") (pintype "passive"))
      (node (ref "C137") (pin "2") (pinfunction "2_2") (pintype "passive"))
      (node (ref "C138") (pin "2") (pinfunction "2_2") (pintype "passive"))
      (node (ref "C139") (pin "2") (pinfunction "2_2") (pintype "passive"))
      (node (ref "C140") (pin "2") (pinfunction "2_2") (pintype "passive"))
      (node (ref "C141") (pin "2") (pinfunction "2_2") (pintype "passive"))
      (node (ref "U7") (pin "N10") (pinfunction "VDD_VPU_3_N10") (pintype "passive"))
      (node (ref "U7") (pin "N8") (pinfunction "VDD_VPU_1_N8") (pintype "passive"))
      (node (ref "U7") (pin "N9") (pinfunction "VDD_VPU_2_N9") (pintype "passive"))
      (node (ref "U7") (pin "P10") (pinfunction "VDD_VPU_5_P10") (pintype "passive"))
      (node (ref "U7") (pin "P9") (pinfunction "VDD_VPU_4_P9") (pintype "passive"))
    )
  )
)
